# ESP32-S3_4G_LTE_CAT1_V1_1.net
KiCad netlist of a schematic drawn in EAGLE
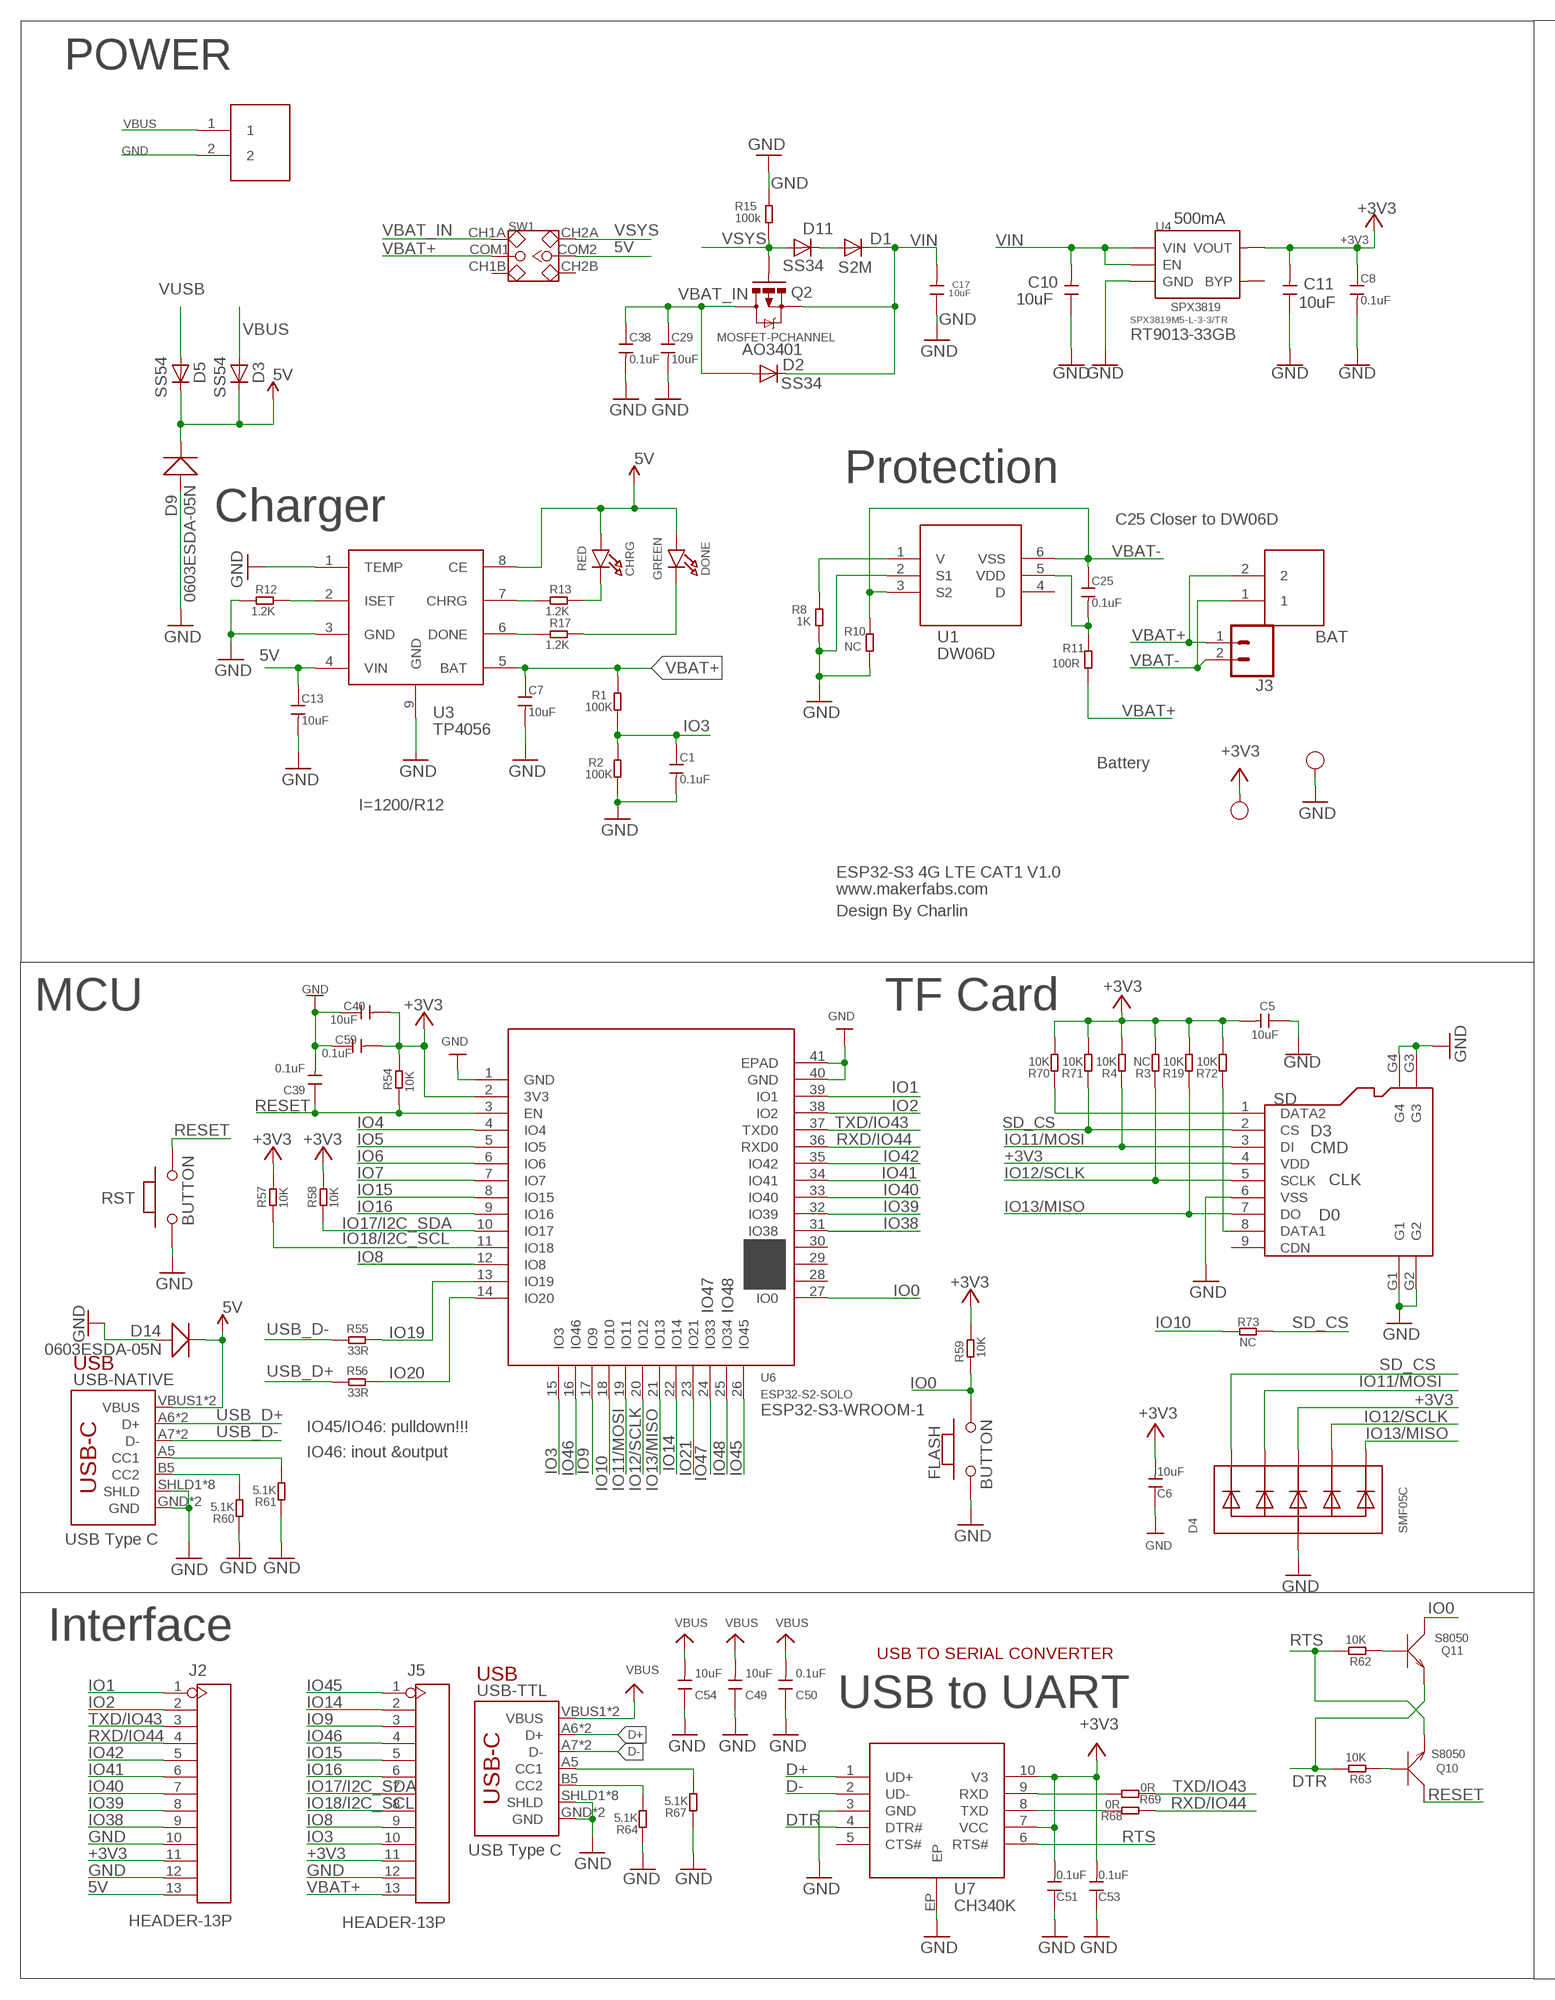
[diagram p0: schematic, sheet 1, part 1 of 2]
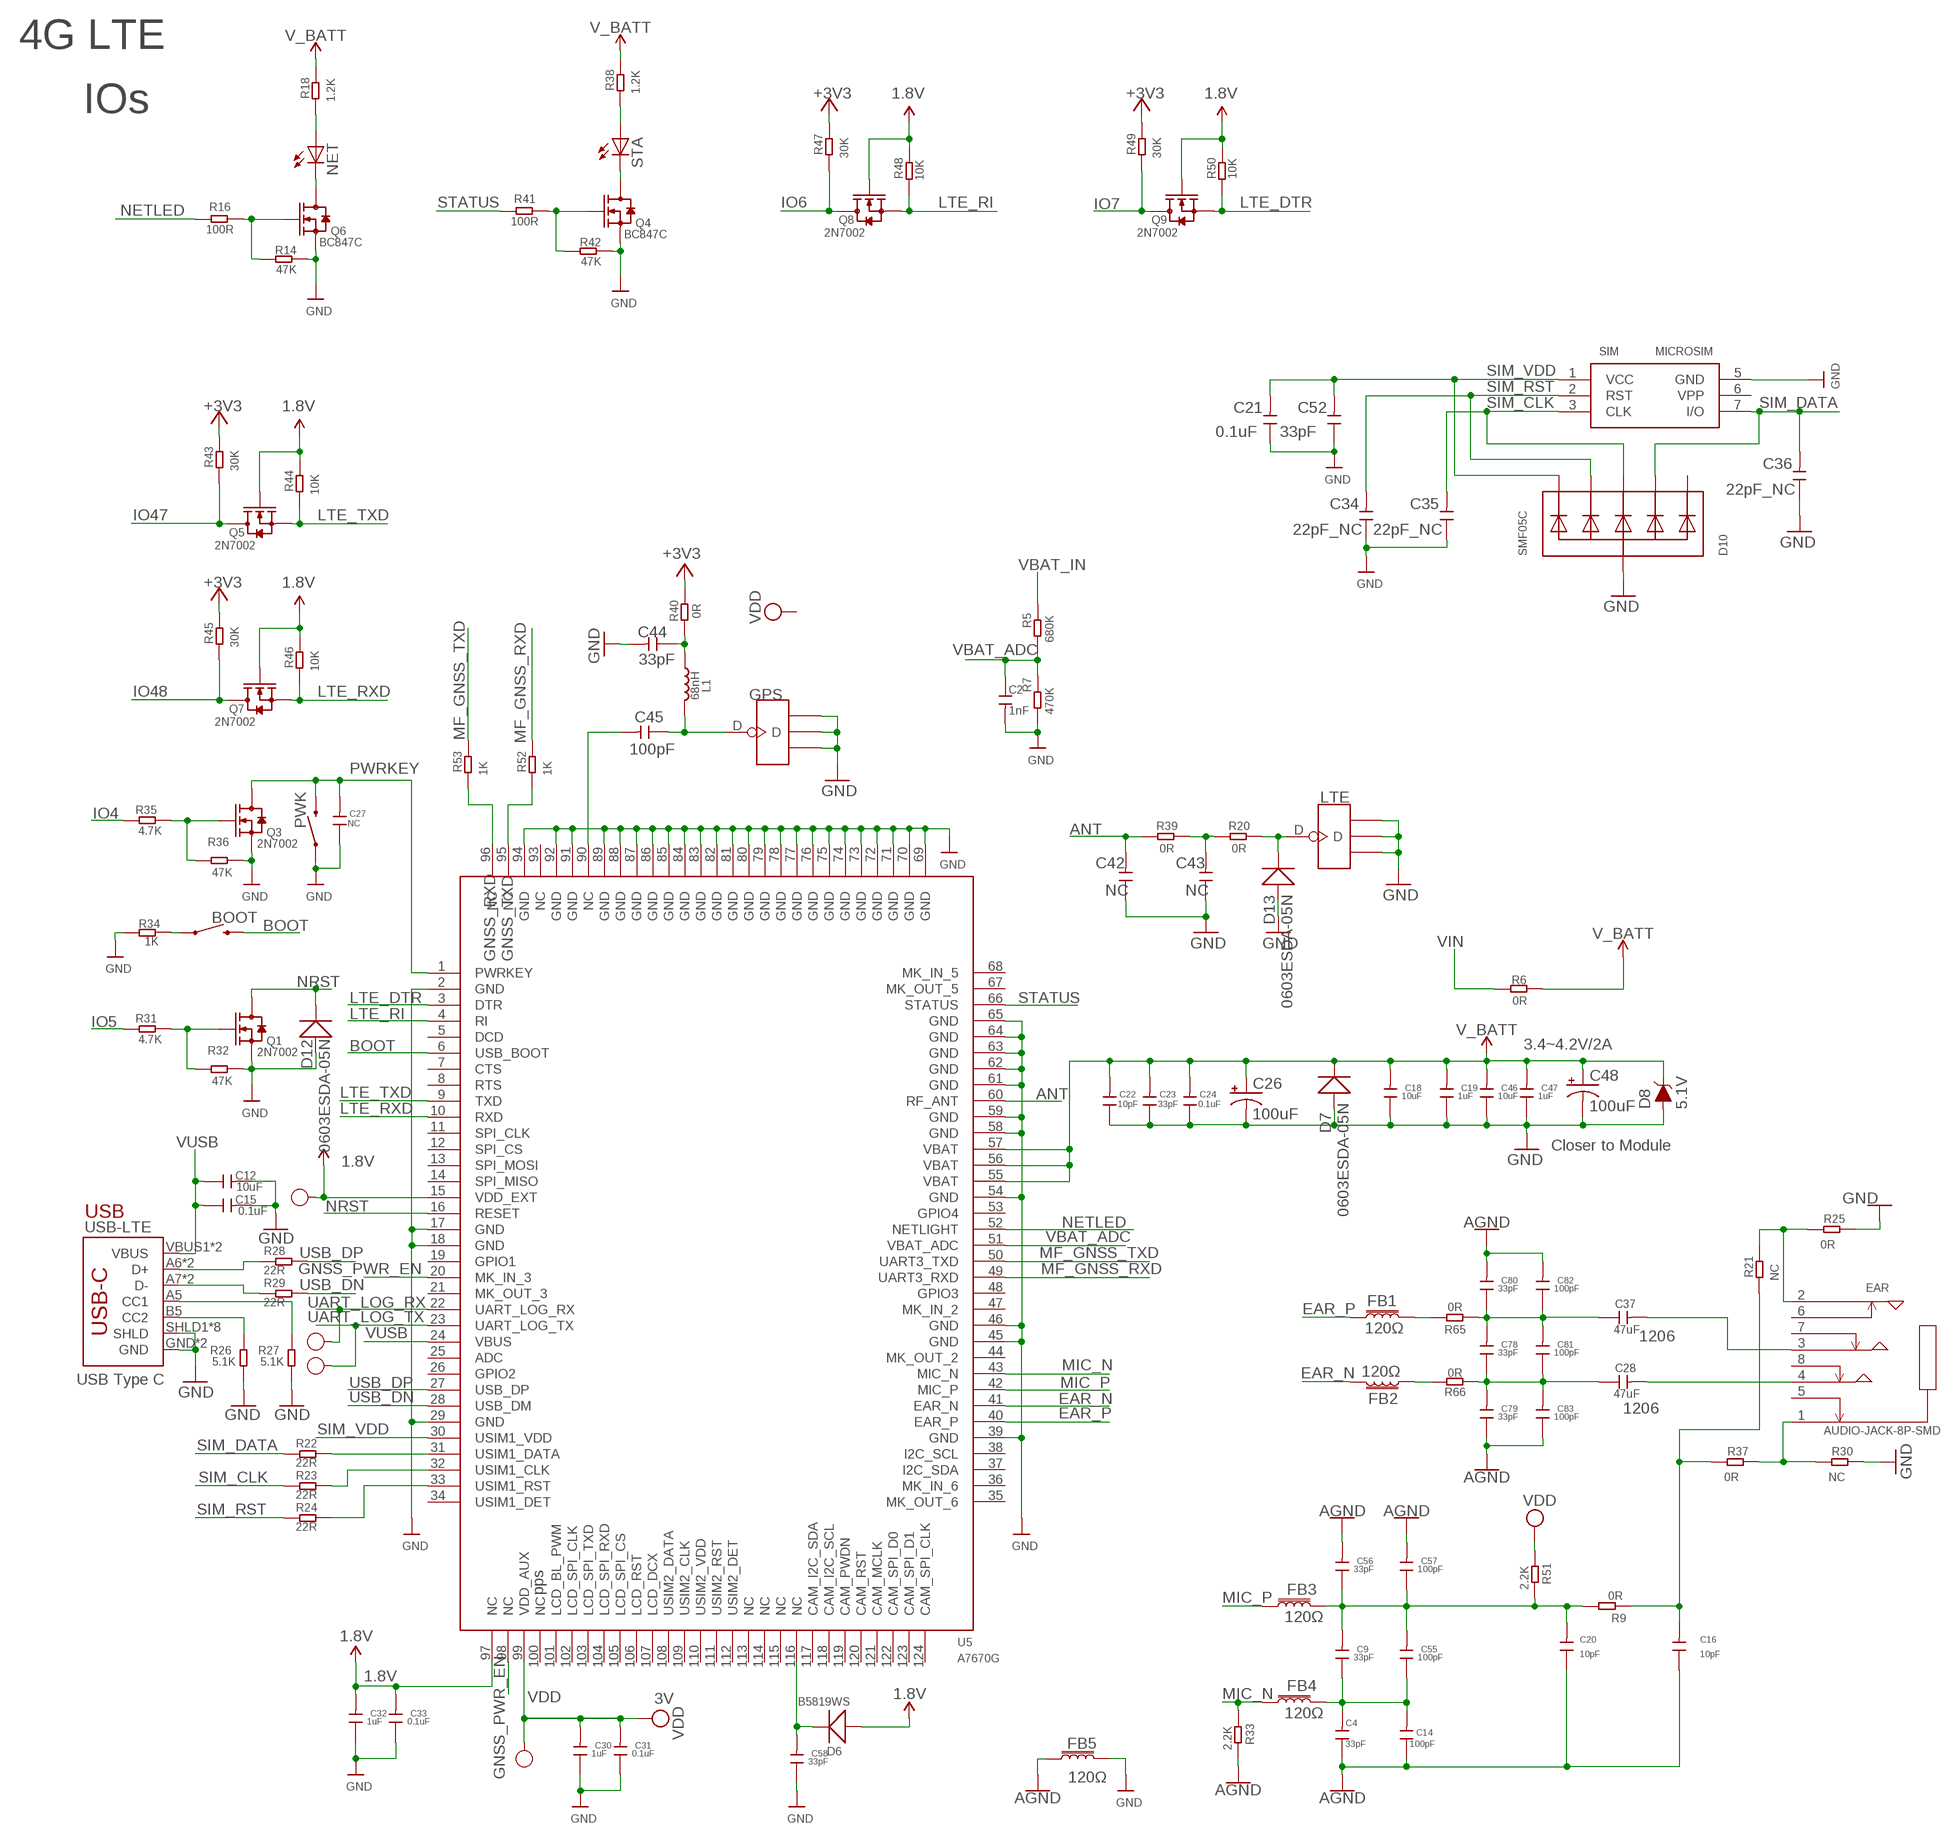
[diagram p1: schematic, sheet 1, part 2 of 2]

(export (version "E")
  (design (tool "Eeschema 10.0.6"))
  (components
    (comp (ref "1V8")
      (value "TEST-POINT'4545'")
      (footprint "eagle-import:TP-D45MIL")
      (fields (field (name "PARTNO") "DNP") (field (name "PARTNO_1") "DNP"))
      (libsource (lib "eagle-import") (part "TEST-POINT'4545'"))
    )
    (comp (ref "3V")
      (value "TEST-POINT'4545'")
      (footprint "eagle-import:TP-D45MIL")
      (fields (field (name "PARTNO") "DNP") (field (name "PARTNO_1") "DNP"))
      (libsource (lib "eagle-import") (part "TEST-POINT'4545'"))
    )
    (comp (ref "3V3")
      (value "TEST-POINT'4545'")
      (footprint "eagle-import:TP-D45MIL")
      (fields (field (name "PARTNO") "DNP") (field (name "PARTNO_1") "DNP"))
      (libsource (lib "eagle-import") (part "TEST-POINT'4545'"))
    )
    (comp (ref "BAT")
      (value "PH2.0-2P-90-DIP")
      (footprint "eagle-import:PH2.0-2P-90-DIP")
      (libsource (lib "eagle-import") (part "PH2.0-2P-90-DIP"))
    )
    (comp (ref "BOOT")
      (value "MOMENTARY-SWITCH-SPST-SMD-6.0X3.5MM")
      (footprint "eagle-import:TACTILE_SWITCH_SMD_6.0X3.5MM")
      (fields (field (name "PROD_ID") "SWCH-00815") (field (name "SF_SKU") "COM-08229"))
      (libsource (lib "eagle-import") (part "MOMENTARY-SWITCH-SPST-SMD-6.0X3.5MM"))
    )
    (comp (ref "C1")
      (value "0.1uF")
      (footprint "eagle-import:0603")
      (libsource (lib "eagle-import") (part "C-0603"))
    )
    (comp (ref "C2")
      (value "1nF")
      (footprint "eagle-import:0603")
      (libsource (lib "eagle-import") (part "C-0603"))
    )
    (comp (ref "C4")
      (value "33pF")
      (footprint "eagle-import:0603")
      (libsource (lib "eagle-import") (part "C-0603"))
    )
    (comp (ref "C5")
      (value "10uF")
      (footprint "eagle-import:DISCRETE_C0603")
      (libsource (lib "eagle-import") (part "DISCRETE_C-0603"))
    )
    (comp (ref "C6")
      (value "10uF")
      (footprint "eagle-import:DISCRETE_C0603")
      (libsource (lib "eagle-import") (part "DISCRETE_C-0603"))
    )
    (comp (ref "C7")
      (value "10uF")
      (footprint "eagle-import:0603")
      (libsource (lib "eagle-import") (part "C-0603"))
    )
    (comp (ref "C8")
      (value "0.1uF")
      (footprint "eagle-import:0603")
      (libsource (lib "eagle-import") (part "C-0603"))
    )
    (comp (ref "C9")
      (value "33pF")
      (footprint "eagle-import:0603")
      (libsource (lib "eagle-import") (part "C-0603"))
    )
    (comp (ref "C10")
      (value "10uF")
      (footprint "eagle-import:0603")
      (libsource (lib "eagle-import") (part "C-0603"))
    )
    (comp (ref "C11")
      (value "10uF")
      (footprint "eagle-import:0603")
      (libsource (lib "eagle-import") (part "C-0603"))
    )
    (comp (ref "C12")
      (value "10uF")
      (footprint "eagle-import:0603")
      (libsource (lib "eagle-import") (part "C-0603"))
    )
    (comp (ref "C13")
      (value "10uF")
      (footprint "eagle-import:0603")
      (libsource (lib "eagle-import") (part "C-0603"))
    )
    (comp (ref "C14")
      (value "100pF")
      (footprint "eagle-import:0603")
      (libsource (lib "eagle-import") (part "C-0603"))
    )
    (comp (ref "C15")
      (value "0.1uF")
      (footprint "eagle-import:0603")
      (libsource (lib "eagle-import") (part "C-0603"))
    )
    (comp (ref "C16")
      (value "10pF")
      (footprint "eagle-import:0603")
      (libsource (lib "eagle-import") (part "C-0603"))
    )
    (comp (ref "C17")
      (value "10uF")
      (footprint "eagle-import:0603")
      (libsource (lib "eagle-import") (part "C-0603"))
    )
    (comp (ref "C18")
      (value "10uF")
      (footprint "eagle-import:0603")
      (libsource (lib "eagle-import") (part "C-0603"))
    )
    (comp (ref "C19")
      (value "1uF")
      (footprint "eagle-import:0603")
      (libsource (lib "eagle-import") (part "C-0603"))
    )
    (comp (ref "C20")
      (value "10pF")
      (footprint "eagle-import:0603")
      (libsource (lib "eagle-import") (part "C-0603"))
    )
    (comp (ref "C21")
      (value "0.1uF")
      (footprint "eagle-import:0603")
      (libsource (lib "eagle-import") (part "C-0603"))
    )
    (comp (ref "C22")
      (value "10pF")
      (footprint "eagle-import:0603")
      (libsource (lib "eagle-import") (part "C-0603"))
    )
    (comp (ref "C23")
      (value "33pF")
      (footprint "eagle-import:0603")
      (libsource (lib "eagle-import") (part "C-0603"))
    )
    (comp (ref "C24")
      (value "0.1uF")
      (footprint "eagle-import:0603")
      (libsource (lib "eagle-import") (part "C-0603"))
    )
    (comp (ref "C25")
      (value "0.1uF")
      (footprint "eagle-import:0603")
      (libsource (lib "eagle-import") (part "C-0603"))
    )
    (comp (ref "C26")
      (value "100uF")
      (footprint "eagle-import:EIA3528")
      (fields (field (name "PROD_ID") "CAP-10790"))
      (libsource (lib "eagle-import") (part "68UF-POLAR-EIA3528-10V-10%(TANT)"))
    )
    (comp (ref "C27")
      (value "NC")
      (footprint "eagle-import:0603")
      (libsource (lib "eagle-import") (part "C-0603"))
    )
    (comp (ref "C28")
      (value "47uF")
      (footprint "eagle-import:DISCRETE_C1206")
      (libsource (lib "eagle-import") (part "DISCRETE_C-1206"))
    )
    (comp (ref "C29")
      (value "10uF")
      (footprint "eagle-import:0603")
      (libsource (lib "eagle-import") (part "C-0603"))
    )
    (comp (ref "C30")
      (value "1uF")
      (footprint "eagle-import:0603")
      (libsource (lib "eagle-import") (part "C-0603"))
    )
    (comp (ref "C31")
      (value "0.1uF")
      (footprint "eagle-import:0603")
      (libsource (lib "eagle-import") (part "C-0603"))
    )
    (comp (ref "C32")
      (value "1uF")
      (footprint "eagle-import:0603")
      (libsource (lib "eagle-import") (part "C-0603"))
    )
    (comp (ref "C33")
      (value "0.1uF")
      (footprint "eagle-import:0603")
      (libsource (lib "eagle-import") (part "C-0603"))
    )
    (comp (ref "C34")
      (value "22pF_NC")
      (footprint "eagle-import:0603")
      (libsource (lib "eagle-import") (part "C-0603"))
    )
    (comp (ref "C35")
      (value "22pF_NC")
      (footprint "eagle-import:0603")
      (libsource (lib "eagle-import") (part "C-0603"))
    )
    (comp (ref "C36")
      (value "22pF_NC")
      (footprint "eagle-import:0603")
      (libsource (lib "eagle-import") (part "C-0603"))
    )
    (comp (ref "C37")
      (value "47uF")
      (footprint "eagle-import:DISCRETE_C1206")
      (libsource (lib "eagle-import") (part "DISCRETE_C-1206"))
    )
    (comp (ref "C38")
      (value "0.1uF")
      (footprint "eagle-import:0603")
      (libsource (lib "eagle-import") (part "C-0603"))
    )
    (comp (ref "C39")
      (value "0.1uF")
      (footprint "eagle-import:DISCRETE_C0603")
      (libsource (lib "eagle-import") (part "DISCRETE_C-0603"))
    )
    (comp (ref "C40")
      (value "10uF")
      (footprint "eagle-import:DISCRETE_C0603")
      (libsource (lib "eagle-import") (part "DISCRETE_C-0603"))
    )
    (comp (ref "C42")
      (value "NC")
      (footprint "eagle-import:0603")
      (libsource (lib "eagle-import") (part "C-0603"))
    )
    (comp (ref "C43")
      (value "NC")
      (footprint "eagle-import:0603")
      (libsource (lib "eagle-import") (part "C-0603"))
    )
    (comp (ref "C44")
      (value "33pF")
      (footprint "eagle-import:0603")
      (libsource (lib "eagle-import") (part "C-0603"))
    )
    (comp (ref "C45")
      (value "100pF")
      (footprint "eagle-import:0603")
      (libsource (lib "eagle-import") (part "C-0603"))
    )
    (comp (ref "C46")
      (value "10uF")
      (footprint "eagle-import:0603")
      (libsource (lib "eagle-import") (part "C-0603"))
    )
    (comp (ref "C47")
      (value "1uF")
      (footprint "eagle-import:0603")
      (libsource (lib "eagle-import") (part "C-0603"))
    )
    (comp (ref "C48")
      (value "100uF")
      (footprint "eagle-import:EIA3528")
      (libsource (lib "eagle-import") (part "68UF-POLAR-EIA3528-10V-10%(TANT)"))
    )
    (comp (ref "C49")
      (value "10uF")
      (footprint "eagle-import:DISCRETE_C0603")
      (libsource (lib "eagle-import") (part "DISCRETE_C-0603"))
    )
    (comp (ref "C50")
      (value "0.1uF")
      (footprint "eagle-import:DISCRETE_C0603")
      (libsource (lib "eagle-import") (part "DISCRETE_C-0603"))
    )
    (comp (ref "C51")
      (value "0.1uF")
      (footprint "eagle-import:DISCRETE_C0603")
      (libsource (lib "eagle-import") (part "DISCRETE_C-0603"))
    )
    (comp (ref "C52")
      (value "33pF")
      (footprint "eagle-import:0603")
      (libsource (lib "eagle-import") (part "C-0603"))
    )
    (comp (ref "C53")
      (value "0.1uF")
      (footprint "eagle-import:DISCRETE_C0603")
      (libsource (lib "eagle-import") (part "DISCRETE_C-0603"))
    )
    (comp (ref "C54")
      (value "10uF")
      (footprint "eagle-import:DISCRETE_C0603")
      (libsource (lib "eagle-import") (part "DISCRETE_C-0603"))
    )
    (comp (ref "C55")
      (value "100pF")
      (footprint "eagle-import:0603")
      (libsource (lib "eagle-import") (part "C-0603"))
    )
    (comp (ref "C56")
      (value "33pF")
      (footprint "eagle-import:0603")
      (libsource (lib "eagle-import") (part "C-0603"))
    )
    (comp (ref "C57")
      (value "100pF")
      (footprint "eagle-import:0603")
      (libsource (lib "eagle-import") (part "C-0603"))
    )
    (comp (ref "C58")
      (value "33pF")
      (footprint "eagle-import:0603")
      (libsource (lib "eagle-import") (part "C-0603"))
    )
    (comp (ref "C59")
      (value "0.1uF")
      (footprint "eagle-import:DISCRETE_C0603")
      (libsource (lib "eagle-import") (part "DISCRETE_C-0603"))
    )
    (comp (ref "C78")
      (value "33pF")
      (footprint "eagle-import:0603")
      (libsource (lib "eagle-import") (part "C-0603"))
    )
    (comp (ref "C79")
      (value "33pF")
      (footprint "eagle-import:0603")
      (libsource (lib "eagle-import") (part "C-0603"))
    )
    (comp (ref "C80")
      (value "33pF")
      (footprint "eagle-import:0603")
      (libsource (lib "eagle-import") (part "C-0603"))
    )
    (comp (ref "C81")
      (value "100pF")
      (footprint "eagle-import:0603")
      (libsource (lib "eagle-import") (part "C-0603"))
    )
    (comp (ref "C82")
      (value "100pF")
      (footprint "eagle-import:0603")
      (libsource (lib "eagle-import") (part "C-0603"))
    )
    (comp (ref "C83")
      (value "100pF")
      (footprint "eagle-import:0603")
      (libsource (lib "eagle-import") (part "C-0603"))
    )
    (comp (ref "CHRG")
      (value "RED")
      (footprint "eagle-import:CHIPLED_0805_NOOUTLINE")
      (libsource (lib "eagle-import") (part "LED0805_NOOUTLINE"))
    )
    (comp (ref "D1")
      (value "S2M")
      (footprint "eagle-import:DO-214AC")
      (libsource (lib "eagle-import") (part "DIODE-DO-214AC"))
    )
    (comp (ref "D2")
      (value "SS34")
      (footprint "eagle-import:DO-214AC")
      (libsource (lib "eagle-import") (part "DIODE-DO-214AC"))
    )
    (comp (ref "D3")
      (value "SS54")
      (footprint "eagle-import:DO-214AC")
      (libsource (lib "eagle-import") (part "DIODE-DO-214AC"))
    )
    (comp (ref "D4")
      (value "SMF05C")
      (footprint "eagle-import:SOT363")
      (libsource (lib "eagle-import") (part "TVSARRAY_5LANE"))
    )
    (comp (ref "D5")
      (value "SS54")
      (footprint "eagle-import:DO-214AC")
      (libsource (lib "eagle-import") (part "DIODE-DO-214AC"))
    )
    (comp (ref "D6")
      (value "B5819WS")
      (footprint "eagle-import:SOD323")
      (libsource (lib "eagle-import") (part "D'0805'"))
    )
    (comp (ref "D7")
      (value "0603ESDA-05N")
      (footprint "eagle-import:DISCRETE_SOD523")
      (libsource (lib "eagle-import") (part "DISCRETE_D0603"))
    )
    (comp (ref "D8")
      (value "5.1V")
      (footprint "eagle-import:SOD-323")
      (libsource (lib "eagle-import") (part "DIODE-ZENER-MMSZ5232BS"))
    )
    (comp (ref "D9")
      (value "0603ESDA-05N")
      (footprint "eagle-import:DISCRETE_SOD523")
      (libsource (lib "eagle-import") (part "DISCRETE_D0603"))
    )
    (comp (ref "D10")
      (value "SMF05C")
      (footprint "eagle-import:SOT363")
      (libsource (lib "eagle-import") (part "TVSARRAY_5LANE"))
    )
    (comp (ref "D11")
      (value "SS34")
      (footprint "eagle-import:DO-214AC")
      (libsource (lib "eagle-import") (part "DIODE-DO-214AC"))
    )
    (comp (ref "D12")
      (value "0603ESDA-05N")
      (footprint "eagle-import:DISCRETE_SOD523")
      (libsource (lib "eagle-import") (part "DISCRETE_D0603"))
    )
    (comp (ref "D13")
      (value "0603ESDA-05N")
      (footprint "eagle-import:DISCRETE_SOD523")
      (libsource (lib "eagle-import") (part "DISCRETE_D0603"))
    )
    (comp (ref "D14")
      (value "0603ESDA-05N")
      (footprint "eagle-import:DISCRETE_SOD523")
      (libsource (lib "eagle-import") (part "DISCRETE_D0603"))
    )
    (comp (ref "DONE")
      (value "GREEN")
      (footprint "eagle-import:CHIPLED_0805_NOOUTLINE")
      (libsource (lib "eagle-import") (part "LED0805_NOOUTLINE"))
    )
    (comp (ref "EAR")
      (value "AUDIO-JACK-8P-SMD")
      (footprint "eagle-import:AUDIO8P-SMD-3.5-14.5X6.1X4.0MM")
      (libsource (lib "eagle-import") (part "AUDIO-JACK-8P-SMD'PJ-393'"))
    )
    (comp (ref "FB1")
      (value "120Ω")
      (footprint "eagle-import:0603")
      (libsource (lib "eagle-import") (part "FERRITE_BEAD-0603"))
    )
    (comp (ref "FB2")
      (value "120Ω")
      (footprint "eagle-import:0603")
      (fields (field (name "PROD_ID") "NDUC-13805"))
      (libsource (lib "eagle-import") (part "FERRITE_BEAD-0603"))
    )
    (comp (ref "FB3")
      (value "120Ω")
      (footprint "eagle-import:0603")
      (fields (field (name "PROD_ID") "NDUC-13805"))
      (libsource (lib "eagle-import") (part "FERRITE_BEAD-0603"))
    )
    (comp (ref "FB4")
      (value "120Ω")
      (footprint "eagle-import:0603")
      (fields (field (name "PROD_ID") "NDUC-13805"))
      (libsource (lib "eagle-import") (part "FERRITE_BEAD-0603"))
    )
    (comp (ref "FB5")
      (value "120Ω")
      (footprint "eagle-import:0603")
      (fields (field (name "PROD_ID") "NDUC-13805"))
      (libsource (lib "eagle-import") (part "FERRITE_BEAD-0603"))
    )
    (comp (ref "FLASH")
      (value "BUTTON")
      (footprint "eagle-import:157SW")
      (libsource (lib "eagle-import") (part "PB157"))
    )
    (comp (ref "GND")
      (value "TEST-POINT'4545'")
      (footprint "eagle-import:TP-D45MIL")
      (fields (field (name "PARTNO") "DNP") (field (name "PARTNO_1") "DNP"))
      (libsource (lib "eagle-import") (part "TEST-POINT'4545'"))
    )
    (comp (ref "GPS")
      (value "ANTENNA-U-FL")
      (footprint "eagle-import:4P-U-FL")
      (libsource (lib "eagle-import") (part "ANTENNA-U-FL"))
    )
    (comp (ref "J1")
      (value "PH2.0-2P-90-DIP")
      (footprint "eagle-import:PH2.0-2P-90-DIP")
      (libsource (lib "eagle-import") (part "PH2.0-2P-90-DIP"))
    )
    (comp (ref "J2")
      (value "HEADER-13P")
      (footprint "eagle-import:13P-2.54")
      (libsource (lib "eagle-import") (part "HEADER-13P"))
    )
    (comp (ref "J3")
      (value "CONN_02LOCK")
      (footprint "eagle-import:1X02_LOCK")
      (libsource (lib "eagle-import") (part "CONN_02LOCK"))
    )
    (comp (ref "J5")
      (value "HEADER-13P")
      (footprint "eagle-import:13P-2.54")
      (libsource (lib "eagle-import") (part "HEADER-13P"))
    )
    (comp (ref "L1")
      (value "68nH")
      (footprint "eagle-import:L0603")
      (libsource (lib "eagle-import") (part "L'0603'"))
    )
    (comp (ref "LTE")
      (value "ANTENNA-U-FL")
      (footprint "eagle-import:4P-U-FL")
      (libsource (lib "eagle-import") (part "ANTENNA-U-FL"))
    )
    (comp (ref "NET")
      (value "NET")
      (footprint "eagle-import:CHIP-LED0805")
      (libsource (lib "eagle-import") (part "LEDCHIP-LED0805"))
    )
    (comp (ref "PWK")
      (value "MOMENTARY-SWITCH-SPST-SMD-6.0X3.5MM")
      (footprint "eagle-import:TACTILE_SWITCH_SMD_6.0X3.5MM")
      (libsource (lib "eagle-import") (part "MOMENTARY-SWITCH-SPST-SMD-6.0X3.5MM"))
    )
    (comp (ref "Q1")
      (value "2N7002")
      (footprint "eagle-import:SOT23")
      (libsource (lib "eagle-import") (part "MOSFET-N'SOT23'"))
    )
    (comp (ref "Q2")
      (value "MOSFET-PCHANNEL")
      (footprint "eagle-import:SOT23-3")
      (libsource (lib "eagle-import") (part "MOSFET-PCHANNEL"))
    )
    (comp (ref "Q3")
      (value "2N7002")
      (footprint "eagle-import:SOT23")
      (libsource (lib "eagle-import") (part "MOSFET-N'SOT23'"))
    )
    (comp (ref "Q4")
      (value "BC847C")
      (footprint "eagle-import:SOT23")
      (libsource (lib "eagle-import") (part "MOSFET-N'SOT23'"))
    )
    (comp (ref "Q5")
      (value "2N7002")
      (footprint "eagle-import:SOT23")
      (libsource (lib "eagle-import") (part "MOSFET-N'SOT23'"))
    )
    (comp (ref "Q6")
      (value "BC847C")
      (footprint "eagle-import:SOT23")
      (libsource (lib "eagle-import") (part "MOSFET-N'SOT23'"))
    )
    (comp (ref "Q7")
      (value "2N7002")
      (footprint "eagle-import:SOT23")
      (libsource (lib "eagle-import") (part "MOSFET-N'SOT23'"))
    )
    (comp (ref "Q8")
      (value "2N7002")
      (footprint "eagle-import:SOT23")
      (libsource (lib "eagle-import") (part "MOSFET-N'SOT23'"))
    )
    (comp (ref "Q9")
      (value "2N7002")
      (footprint "eagle-import:SOT23")
      (libsource (lib "eagle-import") (part "MOSFET-N'SOT23'"))
    )
    (comp (ref "Q10")
      (value "S8050")
      (footprint "eagle-import:SOT23")
      (libsource (lib "eagle-import") (part "TRANSISTOR-NPN-SOT23"))
    )
    (comp (ref "Q11")
      (value "S8050")
      (footprint "eagle-import:SOT23")
      (libsource (lib "eagle-import") (part "TRANSISTOR-NPN-SOT23"))
    )
    (comp (ref "R1")
      (value "100K")
      (footprint "eagle-import:R0603")
      (libsource (lib "eagle-import") (part "R-0603"))
    )
    (comp (ref "R2")
      (value "100K")
      (footprint "eagle-import:R0603")
      (libsource (lib "eagle-import") (part "R-0603"))
    )
    (comp (ref "R3")
      (value "NC")
      (footprint "eagle-import:DISCRETE_R0603")
      (libsource (lib "eagle-import") (part "DISCRETE_R-0603"))
    )
    (comp (ref "R4")
      (value "10K")
      (footprint "eagle-import:DISCRETE_R0603")
      (libsource (lib "eagle-import") (part "DISCRETE_R-0603"))
    )
    (comp (ref "R5")
      (value "680K")
      (footprint "eagle-import:R0603")
      (libsource (lib "eagle-import") (part "R-0603"))
    )
    (comp (ref "R6")
      (value "0R")
      (footprint "eagle-import:R0603")
      (libsource (lib "eagle-import") (part "R-0603"))
    )
    (comp (ref "R7")
      (value "470K")
      (footprint "eagle-import:R0603")
      (libsource (lib "eagle-import") (part "R-0603"))
    )
    (comp (ref "R8")
      (value "1K")
      (footprint "eagle-import:R0603")
      (libsource (lib "eagle-import") (part "R-0603"))
    )
    (comp (ref "R9")
      (value "0R")
      (footprint "eagle-import:R0603")
      (libsource (lib "eagle-import") (part "R-0603"))
    )
    (comp (ref "R10")
      (value "NC")
      (footprint "eagle-import:R0603")
      (libsource (lib "eagle-import") (part "R-0603"))
    )
    (comp (ref "R11")
      (value "100R")
      (footprint "eagle-import:R0603")
      (libsource (lib "eagle-import") (part "R-0603"))
    )
    (comp (ref "R12")
      (value "1.2K")
      (footprint "eagle-import:R0603")
      (libsource (lib "eagle-import") (part "R-0603"))
    )
    (comp (ref "R13")
      (value "1.2K")
      (footprint "eagle-import:R0603")
      (libsource (lib "eagle-import") (part "R-0603"))
    )
    (comp (ref "R14")
      (value "47K")
      (footprint "eagle-import:R0603")
      (libsource (lib "eagle-import") (part "R-0603"))
    )
    (comp (ref "R15")
      (value "100k")
      (footprint "eagle-import:R0603")
      (libsource (lib "eagle-import") (part "R-0603"))
    )
    (comp (ref "R16")
      (value "100R")
      (footprint "eagle-import:R0603")
      (libsource (lib "eagle-import") (part "R-0603"))
    )
    (comp (ref "R17")
      (value "1.2K")
      (footprint "eagle-import:R0603")
      (libsource (lib "eagle-import") (part "R-0603"))
    )
    (comp (ref "R18")
      (value "1.2K")
      (footprint "eagle-import:R0603")
      (libsource (lib "eagle-import") (part "R-0603"))
    )
    (comp (ref "R19")
      (value "10K")
      (footprint "eagle-import:DISCRETE_R0603")
      (libsource (lib "eagle-import") (part "DISCRETE_R-0603"))
    )
    (comp (ref "R20")
      (value "0R")
      (footprint "eagle-import:R0603")
      (libsource (lib "eagle-import") (part "R-0603"))
    )
    (comp (ref "R21")
      (value "NC")
      (footprint "eagle-import:R0603")
      (libsource (lib "eagle-import") (part "R-0603"))
    )
    (comp (ref "R22")
      (value "22R")
      (footprint "eagle-import:R0603")
      (libsource (lib "eagle-import") (part "R-0603"))
    )
    (comp (ref "R23")
      (value "22R")
      (footprint "eagle-import:R0603")
      (libsource (lib "eagle-import") (part "R-0603"))
    )
    (comp (ref "R24")
      (value "22R")
      (footprint "eagle-import:R0603")
      (libsource (lib "eagle-import") (part "R-0603"))
    )
    (comp (ref "R25")
      (value "0R")
      (footprint "eagle-import:R0603")
      (libsource (lib "eagle-import") (part "R-0603"))
    )
    (comp (ref "R26")
      (value "5.1K")
      (footprint "eagle-import:R0603")
      (libsource (lib "eagle-import") (part "R-0603"))
    )
    (comp (ref "R27")
      (value "5.1K")
      (footprint "eagle-import:R0603")
      (libsource (lib "eagle-import") (part "R-0603"))
    )
    (comp (ref "R28")
      (value "22R")
      (footprint "eagle-import:R0603")
      (libsource (lib "eagle-import") (part "R-0603"))
    )
    (comp (ref "R29")
      (value "22R")
      (footprint "eagle-import:R0603")
      (libsource (lib "eagle-import") (part "R-0603"))
    )
    (comp (ref "R30")
      (value "NC")
      (footprint "eagle-import:R0603")
      (libsource (lib "eagle-import") (part "R-0603"))
    )
    (comp (ref "R31")
      (value "4.7K")
      (footprint "eagle-import:R0603")
      (libsource (lib "eagle-import") (part "R-0603"))
    )
    (comp (ref "R32")
      (value "47K")
      (footprint "eagle-import:R0603")
      (libsource (lib "eagle-import") (part "R-0603"))
    )
    (comp (ref "R33")
      (value "2.2K")
      (footprint "eagle-import:R0603")
      (libsource (lib "eagle-import") (part "R-0603"))
    )
    (comp (ref "R34")
      (value "1K")
      (footprint "eagle-import:R0603")
      (libsource (lib "eagle-import") (part "R-0603"))
    )
    (comp (ref "R35")
      (value "4.7K")
      (footprint "eagle-import:R0603")
      (libsource (lib "eagle-import") (part "R-0603"))
    )
    (comp (ref "R36")
      (value "47K")
      (footprint "eagle-import:R0603")
      (libsource (lib "eagle-import") (part "R-0603"))
    )
    (comp (ref "R37")
      (value "0R")
      (footprint "eagle-import:R0603")
      (libsource (lib "eagle-import") (part "R-0603"))
    )
    (comp (ref "R38")
      (value "1.2K")
      (footprint "eagle-import:R0603")
      (libsource (lib "eagle-import") (part "R-0603"))
    )
    (comp (ref "R39")
      (value "0R")
      (footprint "eagle-import:R0603")
      (libsource (lib "eagle-import") (part "R-0603"))
    )
    (comp (ref "R40")
      (value "0R")
      (footprint "eagle-import:R0603")
      (libsource (lib "eagle-import") (part "R-0603"))
    )
    (comp (ref "R41")
      (value "100R")
      (footprint "eagle-import:R0603")
      (libsource (lib "eagle-import") (part "R-0603"))
    )
    (comp (ref "R42")
      (value "47K")
      (footprint "eagle-import:R0603")
      (libsource (lib "eagle-import") (part "R-0603"))
    )
    (comp (ref "R43")
      (value "30K")
      (footprint "eagle-import:R0603")
      (libsource (lib "eagle-import") (part "R-0603"))
    )
    (comp (ref "R44")
      (value "10K")
      (footprint "eagle-import:R0603")
      (libsource (lib "eagle-import") (part "R-0603"))
    )
    (comp (ref "R45")
      (value "30K")
      (footprint "eagle-import:R0603")
      (libsource (lib "eagle-import") (part "R-0603"))
    )
    (comp (ref "R46")
      (value "10K")
      (footprint "eagle-import:R0603")
      (libsource (lib "eagle-import") (part "R-0603"))
    )
    (comp (ref "R47")
      (value "30K")
      (footprint "eagle-import:R0603")
      (libsource (lib "eagle-import") (part "R-0603"))
    )
    (comp (ref "R48")
      (value "10K")
      (footprint "eagle-import:R0603")
      (libsource (lib "eagle-import") (part "R-0603"))
    )
    (comp (ref "R49")
      (value "30K")
      (footprint "eagle-import:R0603")
      (libsource (lib "eagle-import") (part "R-0603"))
    )
    (comp (ref "R50")
      (value "10K")
      (footprint "eagle-import:R0603")
      (libsource (lib "eagle-import") (part "R-0603"))
    )
    (comp (ref "R51")
      (value "2.2K")
      (footprint "eagle-import:R0603")
      (libsource (lib "eagle-import") (part "R-0603"))
    )
    (comp (ref "R52")
      (value "1K")
      (footprint "eagle-import:R0603")
      (libsource (lib "eagle-import") (part "R-0603"))
    )
    (comp (ref "R53")
      (value "1K")
      (footprint "eagle-import:R0603")
      (libsource (lib "eagle-import") (part "R-0603"))
    )
    (comp (ref "R54")
      (value "10K")
      (footprint "eagle-import:R0603")
      (libsource (lib "eagle-import") (part "R-0603"))
    )
    (comp (ref "R55")
      (value "33R")
      (footprint "eagle-import:R0603")
      (libsource (lib "eagle-import") (part "R-0603"))
    )
    (comp (ref "R56")
      (value "33R")
      (footprint "eagle-import:R0603")
      (libsource (lib "eagle-import") (part "R-0603"))
    )
    (comp (ref "R57")
      (value "10K")
      (footprint "eagle-import:R0603")
      (libsource (lib "eagle-import") (part "R-0603"))
    )
    (comp (ref "R58")
      (value "10K")
      (footprint "eagle-import:R0603")
      (libsource (lib "eagle-import") (part "R-0603"))
    )
    (comp (ref "R59")
      (value "10K")
      (footprint "eagle-import:R0603")
      (libsource (lib "eagle-import") (part "R-0603"))
    )
    (comp (ref "R60")
      (value "5.1K")
      (footprint "eagle-import:DISCRETE_R0603")
      (libsource (lib "eagle-import") (part "DISCRETE_R-0603"))
    )
    (comp (ref "R61")
      (value "5.1K")
      (footprint "eagle-import:DISCRETE_R0603")
      (libsource (lib "eagle-import") (part "DISCRETE_R-0603"))
    )
    (comp (ref "R62")
      (value "10K")
      (footprint "eagle-import:R0603")
      (libsource (lib "eagle-import") (part "R-0603"))
    )
    (comp (ref "R63")
      (value "10K")
      (footprint "eagle-import:R0603")
      (libsource (lib "eagle-import") (part "R-0603"))
    )
    (comp (ref "R64")
      (value "5.1K")
      (footprint "eagle-import:DISCRETE_R0603")
      (libsource (lib "eagle-import") (part "DISCRETE_R-0603"))
    )
    (comp (ref "R65")
      (value "0R")
      (footprint "eagle-import:R0603")
      (libsource (lib "eagle-import") (part "R-0603"))
    )
    (comp (ref "R66")
      (value "0R")
      (footprint "eagle-import:R0603")
      (libsource (lib "eagle-import") (part "R-0603"))
    )
    (comp (ref "R67")
      (value "5.1K")
      (footprint "eagle-import:DISCRETE_R0603")
      (libsource (lib "eagle-import") (part "DISCRETE_R-0603"))
    )
    (comp (ref "R68")
      (value "0R")
      (footprint "eagle-import:R0603")
      (libsource (lib "eagle-import") (part "R-0603"))
    )
    (comp (ref "R69")
      (value "0R")
      (footprint "eagle-import:R0603")
      (libsource (lib "eagle-import") (part "R-0603"))
    )
    (comp (ref "R70")
      (value "10K")
      (footprint "eagle-import:DISCRETE_R0603")
      (libsource (lib "eagle-import") (part "DISCRETE_R-0603"))
    )
    (comp (ref "R71")
      (value "10K")
      (footprint "eagle-import:DISCRETE_R0603")
      (libsource (lib "eagle-import") (part "DISCRETE_R-0603"))
    )
    (comp (ref "R72")
      (value "10K")
      (footprint "eagle-import:DISCRETE_R0603")
      (libsource (lib "eagle-import") (part "DISCRETE_R-0603"))
    )
    (comp (ref "R73")
      (value "NC")
      (footprint "eagle-import:R0603")
      (libsource (lib "eagle-import") (part "R-0603"))
    )
    (comp (ref "RST")
      (value "BUTTON")
      (footprint "eagle-import:157SW")
      (libsource (lib "eagle-import") (part "PB157"))
    )
    (comp (ref "RX")
      (value "TEST-POINT'4545'")
      (footprint "eagle-import:TP-D45MIL")
      (fields (field (name "PARTNO") "DNP") (field (name "PARTNO_1") "DNP"))
      (libsource (lib "eagle-import") (part "TEST-POINT'4545'"))
    )
    (comp (ref "SD")
      (value "HOLDER-MICROSD-9P")
      (footprint "eagle-import:9P-SMD-W_-RING")
      (libsource (lib "eagle-import") (part "HOLDER-MICROSD-9P"))
    )
    (comp (ref "SIM")
      (value "MICROSIM")
      (footprint "eagle-import:MICROSIM")
      (libsource (lib "eagle-import") (part "MICROSIM"))
    )
    (comp (ref "STA")
      (value "NET")
      (footprint "eagle-import:CHIP-LED0805")
      (libsource (lib "eagle-import") (part "LEDCHIP-LED0805"))
    )
    (comp (ref "SW1")
      (value "SWITCH-2CH-6P")
      (footprint "eagle-import:6P-2CH-2.54-7.6X3.0")
      (libsource (lib "eagle-import") (part "SWITCH-2CH-6P"))
    )
    (comp (ref "TX")
      (value "TEST-POINT'4545'")
      (footprint "eagle-import:TP-D45MIL")
      (fields (field (name "PARTNO") "DNP") (field (name "PARTNO_1") "DNP"))
      (libsource (lib "eagle-import") (part "TEST-POINT'4545'"))
    )
    (comp (ref "U1")
      (value "DW06D")
      (footprint "eagle-import:SOT-23-6")
      (libsource (lib "eagle-import") (part "DW06D"))
    )
    (comp (ref "U3")
      (value "TP4056")
      (footprint "eagle-import:SOP8-1.27P")
      (libsource (lib "eagle-import") (part "TP4056"))
    )
    (comp (ref "U4")
      (value "SPX3819")
      (footprint "eagle-import:SOT23-5")
      (libsource (lib "eagle-import") (part "SPX3819"))
    )
    (comp (ref "U5")
      (value "A7670G")
      (footprint "eagle-import:A7670G")
      (libsource (lib "eagle-import") (part "A7670G"))
    )
    (comp (ref "U6")
      (value "ESP32­S2­SOLO")
      (footprint "eagle-import:ESP32-­S2-­SOLO")
      (libsource (lib "eagle-import") (part "ESP32­S2­SOLO"))
    )
    (comp (ref "U7")
      (value "CH340K")
      (footprint "eagle-import:ESOP-10-EP-150MIL")
      (libsource (lib "eagle-import") (part "CH340K"))
    )
    (comp (ref "USB-LTE")
      (value "USB_C5")
      (footprint "eagle-import:USB-C-16P-5")
      (libsource (lib "eagle-import") (part "USB_C5"))
    )
    (comp (ref "USB-NATIVE")
      (value "USB_C5")
      (footprint "eagle-import:USB-C-16P-5")
      (libsource (lib "eagle-import") (part "USB_C5"))
    )
    (comp (ref "USB-TTL")
      (value "USB_C5")
      (footprint "eagle-import:USB-C-16P-5")
      (libsource (lib "eagle-import") (part "USB_C5"))
    )
  )
  (nets
    (net (code "1") (name "+3V3") (class "Default")
      (node (ref "3V3") (pin "T") (pinfunction "T_T") (pintype "bidirectional"))
      (node (ref "C11") (pin "2") (pinfunction "2_2") (pintype "passive"))
      (node (ref "C40") (pin "2") (pinfunction "2_2") (pintype "passive"))
      (node (ref "C5") (pin "2") (pinfunction "2_2") (pintype "passive"))
      (node (ref "C51") (pin "2") (pinfunction "2_2") (pintype "passive"))
      (node (ref "C53") (pin "2") (pinfunction "2_2") (pintype "passive"))
      (node (ref "C59") (pin "2") (pinfunction "2_2") (pintype "passive"))
      (node (ref "C6") (pin "2") (pinfunction "2_2") (pintype "passive"))
      (node (ref "C8") (pin "1") (pinfunction "1_1") (pintype "passive"))
      (node (ref "D4") (pin "4") (pinfunction "C3_4") (pintype "passive"))
      (node (ref "J2") (pin "11") (pinfunction "11_11") (pintype "bidirectional"))
      (node (ref "J5") (pin "11") (pinfunction "11_11") (pintype "bidirectional"))
      (node (ref "R19") (pin "2") (pinfunction "2_2") (pintype "passive"))
      (node (ref "R3") (pin "2") (pinfunction "2_2") (pintype "passive"))
      (node (ref "R4") (pin "2") (pinfunction "2_2") (pintype "passive"))
      (node (ref "R40") (pin "2") (pinfunction "2_2") (pintype "passive"))
      (node (ref "R43") (pin "2") (pinfunction "2_2") (pintype "passive"))
      (node (ref "R45") (pin "2") (pinfunction "2_2") (pintype "passive"))
      (node (ref "R47") (pin "2") (pinfunction "2_2") (pintype "passive"))
      (node (ref "R49") (pin "2") (pinfunction "2_2") (pintype "passive"))
      (node (ref "R54") (pin "2") (pinfunction "2_2") (pintype "passive"))
      (node (ref "R57") (pin "2") (pinfunction "2_2") (pintype "passive"))
      (node (ref "R58") (pin "2") (pinfunction "2_2") (pintype "passive"))
      (node (ref "R59") (pin "2") (pinfunction "2_2") (pintype "passive"))
      (node (ref "R70") (pin "2") (pinfunction "2_2") (pintype "passive"))
      (node (ref "R71") (pin "2") (pinfunction "2_2") (pintype "passive"))
      (node (ref "R72") (pin "2") (pinfunction "2_2") (pintype "passive"))
      (node (ref "SD") (pin "4") (pinfunction "VDD_4") (pintype "bidirectional"))
      (node (ref "U4") (pin "5") (pinfunction "VOUT_5") (pintype "bidirectional"))
      (node (ref "U6") (pin "2") (pinfunction "3V3_2") (pintype "bidirectional"))
      (node (ref "U7") (pin "10") (pinfunction "V3_10") (pintype "bidirectional"))
      (node (ref "U7") (pin "7") (pinfunction "VCC_7") (pintype "bidirectional"))
    )
    (net (code "2") (name "/ANT") (class "Default")
      (node (ref "C42") (pin "2") (pinfunction "2_2") (pintype "passive"))
      (node (ref "R39") (pin "1") (pinfunction "1_1") (pintype "passive"))
      (node (ref "U5") (pin "60") (pinfunction "RF_ANT_60") (pintype "bidirectional"))
    )
    (net (code "3") (name "/BOOT") (class "Default")
      (node (ref "BOOT") (pin "2") (pinfunction "2_2") (pintype "passive"))
      (node (ref "U5") (pin "6") (pinfunction "USB_BOOT_6") (pintype "bidirectional"))
    )
    (net (code "4") (name "/DTR") (class "Default")
      (node (ref "Q11") (pin "2") (pinfunction "E_2") (pintype "passive"))
      (node (ref "R63") (pin "2") (pinfunction "2_2") (pintype "passive"))
      (node (ref "U7") (pin "4") (pinfunction "DTR#_4") (pintype "bidirectional"))
    )
    (net (code "5") (name "/EAR_N") (class "Default")
      (node (ref "FB2") (pin "2") (pinfunction "2_2") (pintype "passive"))
      (node (ref "U5") (pin "41") (pinfunction "EAR_N_41") (pintype "bidirectional"))
    )
    (net (code "6") (name "/EAR_P") (class "Default")
      (node (ref "FB1") (pin "1") (pinfunction "1_1") (pintype "passive"))
      (node (ref "U5") (pin "40") (pinfunction "EAR_P_40") (pintype "bidirectional"))
    )
    (net (code "7") (name "/GNSS_PWR_EN") (class "Default")
      (node (ref "U5") (pin "20") (pinfunction "MK_IN_3_20") (pintype "bidirectional"))
      (node (ref "U5") (pin "98") (pinfunction "NC_98") (pintype "bidirectional"))
    )
    (net (code "8") (name "/IO0") (class "Default")
      (node (ref "FLASH") (pin "2") (pinfunction "2_2") (pintype "passive"))
      (node (ref "Q11") (pin "3") (pinfunction "C_3") (pintype "passive"))
      (node (ref "R59") (pin "1") (pinfunction "1_1") (pintype "passive"))
      (node (ref "U6") (pin "27") (pinfunction "IO0_27") (pintype "bidirectional"))
    )
    (net (code "9") (name "/IO1") (class "Default")
      (node (ref "J2") (pin "1") (pinfunction "1_1") (pintype "bidirectional"))
      (node (ref "U6") (pin "39") (pinfunction "IO1_39") (pintype "bidirectional"))
    )
    (net (code "10") (name "/IO2") (class "Default")
      (node (ref "J2") (pin "2") (pinfunction "2_2") (pintype "bidirectional"))
      (node (ref "U6") (pin "38") (pinfunction "IO2_38") (pintype "bidirectional"))
    )
    (net (code "11") (name "/IO3") (class "Default")
      (node (ref "C1") (pin "1") (pinfunction "1_1") (pintype "passive"))
      (node (ref "J5") (pin "10") (pinfunction "10_10") (pintype "bidirectional"))
      (node (ref "R1") (pin "1") (pinfunction "1_1") (pintype "passive"))
      (node (ref "R2") (pin "2") (pinfunction "2_2") (pintype "passive"))
      (node (ref "U6") (pin "15") (pinfunction "IO3_15") (pintype "bidirectional"))
    )
    (net (code "12") (name "/IO4") (class "Default")
      (node (ref "R35") (pin "2") (pinfunction "2_2") (pintype "passive"))
      (node (ref "U6") (pin "4") (pinfunction "IO4_4") (pintype "bidirectional"))
    )
    (net (code "13") (name "/IO5") (class "Default")
      (node (ref "R31") (pin "2") (pinfunction "2_2") (pintype "passive"))
      (node (ref "U6") (pin "5") (pinfunction "IO5_5") (pintype "bidirectional"))
    )
    (net (code "14") (name "/IO6") (class "Default")
      (node (ref "Q8") (pin "3") (pinfunction "D_3") (pintype "passive"))
      (node (ref "R47") (pin "1") (pinfunction "1_1") (pintype "passive"))
      (node (ref "U6") (pin "6") (pinfunction "IO6_6") (pintype "bidirectional"))
    )
    (net (code "15") (name "/IO7") (class "Default")
      (node (ref "Q9") (pin "3") (pinfunction "D_3") (pintype "passive"))
      (node (ref "R49") (pin "1") (pinfunction "1_1") (pintype "passive"))
      (node (ref "U6") (pin "7") (pinfunction "IO7_7") (pintype "bidirectional"))
    )
    (net (code "16") (name "/IO8") (class "Default")
      (node (ref "J5") (pin "9") (pinfunction "9_9") (pintype "bidirectional"))
      (node (ref "U6") (pin "12") (pinfunction "IO8_12") (pintype "bidirectional"))
    )
    (net (code "17") (name "/IO9") (class "Default")
      (node (ref "J5") (pin "3") (pinfunction "3_3") (pintype "bidirectional"))
      (node (ref "U6") (pin "17") (pinfunction "IO9_17") (pintype "bidirectional"))
    )
    (net (code "18") (name "/IO10") (class "Default")
      (node (ref "R73") (pin "1") (pinfunction "1_1") (pintype "passive"))
      (node (ref "U6") (pin "18") (pinfunction "IO10_18") (pintype "bidirectional"))
    )
    (net (code "19") (name "/IO11{slash}MOSI") (class "Default")
      (node (ref "D4") (pin "3") (pinfunction "C2_3") (pintype "passive"))
      (node (ref "R4") (pin "1") (pinfunction "1_1") (pintype "passive"))
      (node (ref "SD") (pin "3") (pinfunction "DI_3") (pintype "bidirectional"))
      (node (ref "U6") (pin "19") (pinfunction "IO11_19") (pintype "bidirectional"))
    )
    (net (code "20") (name "/IO12{slash}SCLK") (class "Default")
      (node (ref "D4") (pin "5") (pinfunction "C4_5") (pintype "passive"))
      (node (ref "R3") (pin "1") (pinfunction "1_1") (pintype "passive"))
      (node (ref "SD") (pin "5") (pinfunction "SCLK_5") (pintype "bidirectional"))
      (node (ref "U6") (pin "20") (pinfunction "IO12_20") (pintype "bidirectional"))
    )
    (net (code "21") (name "/IO13{slash}MISO") (class "Default")
      (node (ref "D4") (pin "6") (pinfunction "C5_6") (pintype "passive"))
      (node (ref "R19") (pin "1") (pinfunction "1_1") (pintype "passive"))
      (node (ref "SD") (pin "7") (pinfunction "DO_7") (pintype "bidirectional"))
      (node (ref "U6") (pin "21") (pinfunction "IO13_21") (pintype "bidirectional"))
    )
    (net (code "22") (name "/IO14") (class "Default")
      (node (ref "J5") (pin "2") (pinfunction "2_2") (pintype "bidirectional"))
      (node (ref "U6") (pin "22") (pinfunction "IO14_22") (pintype "bidirectional"))
    )
    (net (code "23") (name "/IO15") (class "Default")
      (node (ref "J5") (pin "5") (pinfunction "5_5") (pintype "bidirectional"))
      (node (ref "U6") (pin "8") (pinfunction "IO15_8") (pintype "bidirectional"))
    )
    (net (code "24") (name "/IO16") (class "Default")
      (node (ref "J5") (pin "6") (pinfunction "6_6") (pintype "bidirectional"))
      (node (ref "U6") (pin "9") (pinfunction "IO16_9") (pintype "bidirectional"))
    )
    (net (code "25") (name "/IO17{slash}I2C_SDA") (class "Default")
      (node (ref "J5") (pin "7") (pinfunction "7_7") (pintype "bidirectional"))
      (node (ref "R58") (pin "1") (pinfunction "1_1") (pintype "passive"))
      (node (ref "U6") (pin "10") (pinfunction "IO17_10") (pintype "bidirectional"))
    )
    (net (code "26") (name "/IO18{slash}I2C_SCL") (class "Default")
      (node (ref "J5") (pin "8") (pinfunction "8_8") (pintype "bidirectional"))
      (node (ref "R57") (pin "1") (pinfunction "1_1") (pintype "passive"))
      (node (ref "U6") (pin "11") (pinfunction "IO18_11") (pintype "bidirectional"))
    )
    (net (code "27") (name "/IO19") (class "Default")
      (node (ref "R55") (pin "2") (pinfunction "2_2") (pintype "passive"))
      (node (ref "U6") (pin "13") (pinfunction "IO19_13") (pintype "bidirectional"))
    )
    (net (code "28") (name "/IO20") (class "Default")
      (node (ref "R56") (pin "2") (pinfunction "2_2") (pintype "passive"))
      (node (ref "U6") (pin "14") (pinfunction "IO20_14") (pintype "bidirectional"))
    )
    (net (code "29") (name "/IO21") (class "Default")
      (node (ref "U6") (pin "23") (pinfunction "IO21_23") (pintype "bidirectional"))
    )
    (net (code "30") (name "/IO38") (class "Default")
      (node (ref "J2") (pin "9") (pinfunction "9_9") (pintype "bidirectional"))
      (node (ref "U6") (pin "31") (pinfunction "IO38_31") (pintype "bidirectional"))
    )
    (net (code "31") (name "/IO39") (class "Default")
      (node (ref "J2") (pin "8") (pinfunction "8_8") (pintype "bidirectional"))
      (node (ref "U6") (pin "32") (pinfunction "IO39_32") (pintype "bidirectional"))
    )
    (net (code "32") (name "/IO40") (class "Default")
      (node (ref "J2") (pin "7") (pinfunction "7_7") (pintype "bidirectional"))
      (node (ref "U6") (pin "33") (pinfunction "IO40_33") (pintype "bidirectional"))
    )
    (net (code "33") (name "/IO41") (class "Default")
      (node (ref "J2") (pin "6") (pinfunction "6_6") (pintype "bidirectional"))
      (node (ref "U6") (pin "34") (pinfunction "IO41_34") (pintype "bidirectional"))
    )
    (net (code "34") (name "/IO42") (class "Default")
      (node (ref "J2") (pin "5") (pinfunction "5_5") (pintype "bidirectional"))
      (node (ref "U6") (pin "35") (pinfunction "IO42_35") (pintype "bidirectional"))
    )
    (net (code "35") (name "/IO45") (class "Default")
      (node (ref "J5") (pin "1") (pinfunction "1_1") (pintype "bidirectional"))
      (node (ref "U6") (pin "26") (pinfunction "IO45_26") (pintype "bidirectional"))
    )
    (net (code "36") (name "/IO46") (class "Default")
      (node (ref "J5") (pin "4") (pinfunction "4_4") (pintype "bidirectional"))
      (node (ref "U6") (pin "16") (pinfunction "IO46_16") (pintype "bidirectional"))
    )
    (net (code "37") (name "/IO47") (class "Default")
      (node (ref "Q5") (pin "3") (pinfunction "D_3") (pintype "passive"))
      (node (ref "R43") (pin "1") (pinfunction "1_1") (pintype "passive"))
      (node (ref "U6") (pin "24") (pinfunction "IO33_24") (pintype "bidirectional"))
    )
    (net (code "38") (name "/IO48") (class "Default")
      (node (ref "Q7") (pin "3") (pinfunction "D_3") (pintype "passive"))
      (node (ref "R45") (pin "1") (pinfunction "1_1") (pintype "passive"))
      (node (ref "U6") (pin "25") (pinfunction "IO34_25") (pintype "bidirectional"))
    )
    (net (code "39") (name "/LTE_DTR") (class "Default")
      (node (ref "Q9") (pin "2") (pinfunction "S_2") (pintype "passive"))
      (node (ref "R50") (pin "1") (pinfunction "1_1") (pintype "passive"))
      (node (ref "U5") (pin "3") (pinfunction "DTR_3") (pintype "bidirectional"))
    )
    (net (code "40") (name "/LTE_RI") (class "Default")
      (node (ref "Q8") (pin "2") (pinfunction "S_2") (pintype "passive"))
      (node (ref "R48") (pin "1") (pinfunction "1_1") (pintype "passive"))
      (node (ref "U5") (pin "4") (pinfunction "RI_4") (pintype "bidirectional"))
    )
    (net (code "41") (name "/LTE_RXD") (class "Default")
      (node (ref "Q7") (pin "2") (pinfunction "S_2") (pintype "passive"))
      (node (ref "R46") (pin "1") (pinfunction "1_1") (pintype "passive"))
      (node (ref "U5") (pin "10") (pinfunction "RXD_10") (pintype "bidirectional"))
    )
    (net (code "42") (name "/LTE_TXD") (class "Default")
      (node (ref "Q5") (pin "2") (pinfunction "S_2") (pintype "passive"))
      (node (ref "R44") (pin "1") (pinfunction "1_1") (pintype "passive"))
      (node (ref "U5") (pin "9") (pinfunction "TXD_9") (pintype "bidirectional"))
    )
    (net (code "43") (name "/MF_GNSS_RXD") (class "Default")
      (node (ref "R52") (pin "2") (pinfunction "2_2") (pintype "passive"))
      (node (ref "U5") (pin "49") (pinfunction "UART3_RXD_49") (pintype "bidirectional"))
    )
    (net (code "44") (name "/MF_GNSS_TXD") (class "Default")
      (node (ref "R53") (pin "2") (pinfunction "2_2") (pintype "passive"))
      (node (ref "U5") (pin "50") (pinfunction "UART3_TXD_50") (pintype "bidirectional"))
    )
    (net (code "45") (name "/MIC_N") (class "Default")
      (node (ref "FB4") (pin "1") (pinfunction "1_1") (pintype "passive"))
      (node (ref "R33") (pin "1") (pinfunction "1_1") (pintype "passive"))
      (node (ref "U5") (pin "43") (pinfunction "MIC_N_43") (pintype "bidirectional"))
    )
    (net (code "46") (name "/MIC_P") (class "Default")
      (node (ref "FB3") (pin "1") (pinfunction "1_1") (pintype "passive"))
      (node (ref "U5") (pin "42") (pinfunction "MIC_P_42") (pintype "bidirectional"))
    )
    (net (code "47") (name "/NETLED") (class "Default")
      (node (ref "R16") (pin "2") (pinfunction "2_2") (pintype "passive"))
      (node (ref "U5") (pin "52") (pinfunction "NETLIGHT_52") (pintype "bidirectional"))
    )
    (net (code "48") (name "/NRST") (class "Default")
      (node (ref "D12") (pin "-") (pinfunction "-_-") (pintype "passive"))
      (node (ref "Q1") (pin "3") (pinfunction "D_3") (pintype "passive"))
      (node (ref "U5") (pin "16") (pinfunction "RESET_16") (pintype "bidirectional"))
    )
    (net (code "49") (name "/PWRKEY") (class "Default")
      (node (ref "C27") (pin "2") (pinfunction "2_2") (pintype "passive"))
      (node (ref "PWK") (pin "2") (pinfunction "2_2") (pintype "passive"))
      (node (ref "Q3") (pin "3") (pinfunction "D_3") (pintype "passive"))
      (node (ref "U5") (pin "1") (pinfunction "PWRKEY_1") (pintype "bidirectional"))
    )
    (net (code "50") (name "/RESET") (class "Default")
      (node (ref "C39") (pin "1") (pinfunction "1_1") (pintype "passive"))
      (node (ref "Q10") (pin "3") (pinfunction "C_3") (pintype "passive"))
      (node (ref "R54") (pin "1") (pinfunction "1_1") (pintype "passive"))
      (node (ref "RST") (pin "2") (pinfunction "2_2") (pintype "passive"))
      (node (ref "U6") (pin "3") (pinfunction "EN_3") (pintype "bidirectional"))
    )
    (net (code "51") (name "/RTS") (class "Default")
      (node (ref "Q10") (pin "2") (pinfunction "E_2") (pintype "passive"))
      (node (ref "R62") (pin "2") (pinfunction "2_2") (pintype "passive"))
      (node (ref "U7") (pin "6") (pinfunction "RTS#_6") (pintype "bidirectional"))
    )
    (net (code "52") (name "/RXD{slash}IO44") (class "Default")
      (node (ref "J2") (pin "4") (pinfunction "4_4") (pintype "bidirectional"))
      (node (ref "R68") (pin "1") (pinfunction "1_1") (pintype "passive"))
      (node (ref "U6") (pin "36") (pinfunction "RXD0_36") (pintype "bidirectional"))
    )
    (net (code "53") (name "/SD_CS") (class "Default")
      (node (ref "D4") (pin "1") (pinfunction "C1_1") (pintype "passive"))
      (node (ref "R71") (pin "1") (pinfunction "1_1") (pintype "passive"))
      (node (ref "R73") (pin "2") (pinfunction "2_2") (pintype "passive"))
      (node (ref "SD") (pin "2") (pinfunction "CS_2") (pintype "bidirectional"))
    )
    (net (code "54") (name "/SIM_CLK") (class "Default")
      (node (ref "C35") (pin "2") (pinfunction "2_2") (pintype "passive"))
      (node (ref "D10") (pin "4") (pinfunction "C3_4") (pintype "passive"))
      (node (ref "R23") (pin "2") (pinfunction "2_2") (pintype "passive"))
      (node (ref "SIM") (pin "3") (pinfunction "CLK_3") (pintype "bidirectional"))
    )
    (net (code "55") (name "/SIM_DATA") (class "Default")
      (node (ref "C36") (pin "2") (pinfunction "2_2") (pintype "passive"))
      (node (ref "D10") (pin "3") (pinfunction "C2_3") (pintype "passive"))
      (node (ref "R22") (pin "2") (pinfunction "2_2") (pintype "passive"))
      (node (ref "SIM") (pin "7") (pinfunction "I/O_7") (pintype "bidirectional"))
    )
    (net (code "56") (name "/SIM_RST") (class "Default")
      (node (ref "C34") (pin "2") (pinfunction "2_2") (pintype "passive"))
      (node (ref "D10") (pin "5") (pinfunction "C4_5") (pintype "passive"))
      (node (ref "R24") (pin "2") (pinfunction "2_2") (pintype "passive"))
      (node (ref "SIM") (pin "2") (pinfunction "RST_2") (pintype "bidirectional"))
    )
    (net (code "57") (name "/SIM_VDD") (class "Default")
      (node (ref "C21") (pin "2") (pinfunction "2_2") (pintype "passive"))
      (node (ref "C52") (pin "2") (pinfunction "2_2") (pintype "passive"))
      (node (ref "D10") (pin "6") (pinfunction "C5_6") (pintype "passive"))
      (node (ref "SIM") (pin "1") (pinfunction "VCC_1") (pintype "bidirectional"))
      (node (ref "U5") (pin "30") (pinfunction "USIM1_VDD_30") (pintype "bidirectional"))
    )
    (net (code "58") (name "/STATUS") (class "Default")
      (node (ref "R41") (pin "2") (pinfunction "2_2") (pintype "passive"))
      (node (ref "U5") (pin "66") (pinfunction "STATUS_66") (pintype "bidirectional"))
    )
    (net (code "59") (name "/TXD{slash}IO43") (class "Default")
      (node (ref "J2") (pin "3") (pinfunction "3_3") (pintype "bidirectional"))
      (node (ref "R69") (pin "1") (pinfunction "1_1") (pintype "passive"))
      (node (ref "U6") (pin "37") (pinfunction "TXD0_37") (pintype "bidirectional"))
    )
    (net (code "60") (name "/UART_LOG_RX") (class "Default")
      (node (ref "RX") (pin "T") (pinfunction "T_T") (pintype "bidirectional"))
      (node (ref "U5") (pin "22") (pinfunction "UART_LOG_RX_22") (pintype "bidirectional"))
    )
    (net (code "61") (name "/UART_LOG_TX") (class "Default")
      (node (ref "TX") (pin "T") (pinfunction "T_T") (pintype "bidirectional"))
      (node (ref "U5") (pin "23") (pinfunction "UART_LOG_TX_23") (pintype "bidirectional"))
    )
    (net (code "62") (name "/USB_D+") (class "Default")
      (node (ref "R56") (pin "1") (pinfunction "1_1") (pintype "passive"))
      (node (ref "USB-NATIVE") (pin "A6") (pinfunction "D+_A6") (pintype "bidirectional"))
      (node (ref "USB-NATIVE") (pin "B6") (pinfunction "D+_B6") (pintype "bidirectional"))
    )
    (net (code "63") (name "/USB_D-") (class "Default")
      (node (ref "R55") (pin "1") (pinfunction "1_1") (pintype "passive"))
      (node (ref "USB-NATIVE") (pin "A7") (pinfunction "D-_A7") (pintype "bidirectional"))
      (node (ref "USB-NATIVE") (pin "B7") (pinfunction "D-_B7") (pintype "bidirectional"))
    )
    (net (code "64") (name "/USB_DN") (class "Default")
      (node (ref "R29") (pin "1") (pinfunction "1_1") (pintype "passive"))
      (node (ref "U5") (pin "28") (pinfunction "USB_DM_28") (pintype "bidirectional"))
    )
    (net (code "65") (name "/USB_DP") (class "Default")
      (node (ref "R28") (pin "1") (pinfunction "1_1") (pintype "passive"))
      (node (ref "U5") (pin "27") (pinfunction "USB_DP_27") (pintype "bidirectional"))
    )
    (net (code "66") (name "/VBAT-") (class "Default")
      (node (ref "BAT") (pin "1") (pinfunction "1_1") (pintype "bidirectional"))
      (node (ref "C25") (pin "1") (pinfunction "1_1") (pintype "passive"))
      (node (ref "J3") (pin "2") (pinfunction "2_2") (pintype "passive"))
      (node (ref "R10") (pin "2") (pinfunction "2_2") (pintype "passive"))
      (node (ref "U1") (pin "3") (pinfunction "S2_3") (pintype "bidirectional"))
      (node (ref "U1") (pin "6") (pinfunction "VSS_6") (pintype "bidirectional"))
    )
    (net (code "67") (name "/VBAT_ADC") (class "Default")
      (node (ref "C2") (pin "1") (pinfunction "1_1") (pintype "passive"))
      (node (ref "R5") (pin "1") (pinfunction "1_1") (pintype "passive"))
      (node (ref "R7") (pin "2") (pinfunction "2_2") (pintype "passive"))
      (node (ref "U5") (pin "51") (pinfunction "VBAT_ADC_51") (pintype "bidirectional"))
    )
    (net (code "68") (name "/VBAT_IN") (class "Default")
      (node (ref "C29") (pin "1") (pinfunction "1_1") (pintype "passive"))
      (node (ref "C38") (pin "1") (pinfunction "1_1") (pintype "passive"))
      (node (ref "D2") (pin "A") (pinfunction "A_A") (pintype "passive"))
      (node (ref "Q2") (pin "3") (pinfunction "D_3") (pintype "passive"))
      (node (ref "R5") (pin "2") (pinfunction "2_2") (pintype "passive"))
      (node (ref "SW1") (pin "CH1A") (pinfunction "CH1A_CH1A") (pintype "bidirectional"))
    )
    (net (code "69") (name "/VIN") (class "Default")
      (node (ref "C10") (pin "2") (pinfunction "2_2") (pintype "passive"))
      (node (ref "C17") (pin "2") (pinfunction "2_2") (pintype "passive"))
      (node (ref "D1") (pin "C") (pinfunction "C_C") (pintype "passive"))
      (node (ref "D2") (pin "C") (pinfunction "C_C") (pintype "passive"))
      (node (ref "Q2") (pin "2") (pinfunction "S_2") (pintype "passive"))
      (node (ref "R6") (pin "2") (pinfunction "2_2") (pintype "passive"))
      (node (ref "U4") (pin "1") (pinfunction "VIN_1") (pintype "bidirectional"))
      (node (ref "U4") (pin "3") (pinfunction "EN_3") (pintype "bidirectional"))
    )
    (net (code "70") (name "/VSYS") (class "Default")
      (node (ref "D11") (pin "A") (pinfunction "A_A") (pintype "passive"))
      (node (ref "Q2") (pin "1") (pinfunction "G_1") (pintype "passive"))
      (node (ref "R15") (pin "1") (pinfunction "1_1") (pintype "passive"))
      (node (ref "SW1") (pin "CH2A") (pinfunction "CH2A_CH2A") (pintype "bidirectional"))
    )
    (net (code "71") (name "/VUSB") (class "Default")
      (node (ref "C12") (pin "1") (pinfunction "1_1") (pintype "passive"))
      (node (ref "C15") (pin "1") (pinfunction "1_1") (pintype "passive"))
      (node (ref "D5") (pin "A") (pinfunction "A_A") (pintype "passive"))
      (node (ref "U5") (pin "24") (pinfunction "VBUS_24") (pintype "bidirectional"))
      (node (ref "USB-LTE") (pin "VBUS1") (pinfunction "VBUS_VBUS1") (pintype "bidirectional"))
      (node (ref "USB-LTE") (pin "VBUS2") (pinfunction "VBUS_VBUS2") (pintype "bidirectional"))
    )
    (net (code "72") (name "1.8V") (class "Default")
      (node (ref "1V8") (pin "T") (pinfunction "T_T") (pintype "bidirectional"))
      (node (ref "C32") (pin "2") (pinfunction "2_2") (pintype "passive"))
      (node (ref "C33") (pin "2") (pinfunction "2_2") (pintype "passive"))
      (node (ref "D6") (pin "+") (pinfunction "+_+") (pintype "passive"))
      (node (ref "Q5") (pin "1") (pinfunction "G_1") (pintype "passive"))
      (node (ref "Q7") (pin "1") (pinfunction "G_1") (pintype "passive"))
      (node (ref "Q8") (pin "1") (pinfunction "G_1") (pintype "passive"))
      (node (ref "Q9") (pin "1") (pinfunction "G_1") (pintype "passive"))
      (node (ref "R44") (pin "2") (pinfunction "2_2") (pintype "passive"))
      (node (ref "R46") (pin "2") (pinfunction "2_2") (pintype "passive"))
      (node (ref "R48") (pin "2") (pinfunction "2_2") (pintype "passive"))
      (node (ref "R50") (pin "2") (pinfunction "2_2") (pintype "passive"))
      (node (ref "U5") (pin "15") (pinfunction "VDD_EXT_15") (pintype "bidirectional"))
      (node (ref "U5") (pin "97") (pinfunction "NC_97") (pintype "bidirectional"))
    )
    (net (code "73") (name "5V") (class "Default")
      (node (ref "C13") (pin "1") (pinfunction "1_1") (pintype "passive"))
      (node (ref "CHRG") (pin "A") (pinfunction "A_A") (pintype "passive"))
      (node (ref "D14") (pin "-") (pinfunction "-_-") (pintype "passive"))
      (node (ref "D3") (pin "C") (pinfunction "C_C") (pintype "passive"))
      (node (ref "D5") (pin "C") (pinfunction "C_C") (pintype "passive"))
      (node (ref "D9") (pin "-") (pinfunction "-_-") (pintype "passive"))
      (node (ref "DONE") (pin "A") (pinfunction "A_A") (pintype "passive"))
      (node (ref "J2") (pin "13") (pinfunction "13_13") (pintype "bidirectional"))
      (node (ref "SW1") (pin "COM2") (pinfunction "COM2_COM2") (pintype "bidirectional"))
      (node (ref "U3") (pin "4") (pinfunction "VIN_4") (pintype "bidirectional"))
      (node (ref "U3") (pin "8") (pinfunction "CE_8") (pintype "bidirectional"))
      (node (ref "USB-NATIVE") (pin "VBUS1") (pinfunction "VBUS_VBUS1") (pintype "bidirectional"))
      (node (ref "USB-NATIVE") (pin "VBUS2") (pinfunction "VBUS_VBUS2") (pintype "bidirectional"))
    )
    (net (code "74") (name "AGND") (class "Default")
      (node (ref "C14") (pin "1") (pinfunction "1_1") (pintype "passive"))
      (node (ref "C16") (pin "1") (pinfunction "1_1") (pintype "passive"))
      (node (ref "C20") (pin "1") (pinfunction "1_1") (pintype "passive"))
      (node (ref "C4") (pin "1") (pinfunction "1_1") (pintype "passive"))
      (node (ref "C56") (pin "2") (pinfunction "2_2") (pintype "passive"))
      (node (ref "C57") (pin "2") (pinfunction "2_2") (pintype "passive"))
      (node (ref "C79") (pin "1") (pinfunction "1_1") (pintype "passive"))
      (node (ref "C80") (pin "2") (pinfunction "2_2") (pintype "passive"))
      (node (ref "C82") (pin "2") (pinfunction "2_2") (pintype "passive"))
      (node (ref "C83") (pin "1") (pinfunction "1_1") (pintype "passive"))
      (node (ref "FB5") (pin "1") (pinfunction "1_1") (pintype "passive"))
      (node (ref "R33") (pin "2") (pinfunction "2_2") (pintype "passive"))
    )
    (net (code "75") (name "D+") (class "Default")
      (node (ref "U7") (pin "1") (pinfunction "UD+_1") (pintype "bidirectional"))
      (node (ref "USB-TTL") (pin "A6") (pinfunction "D+_A6") (pintype "bidirectional"))
      (node (ref "USB-TTL") (pin "B6") (pinfunction "D+_B6") (pintype "bidirectional"))
    )
    (net (code "76") (name "D-") (class "Default")
      (node (ref "U7") (pin "2") (pinfunction "UD-_2") (pintype "bidirectional"))
      (node (ref "USB-TTL") (pin "A7") (pinfunction "D-_A7") (pintype "bidirectional"))
      (node (ref "USB-TTL") (pin "B7") (pinfunction "D-_B7") (pintype "bidirectional"))
    )
    (net (code "77") (name "GND") (class "Default")
      (node (ref "C1") (pin "2") (pinfunction "2_2") (pintype "passive"))
      (node (ref "C10") (pin "1") (pinfunction "1_1") (pintype "passive"))
      (node (ref "C11") (pin "1") (pinfunction "1_1") (pintype "passive"))
      (node (ref "C12") (pin "2") (pinfunction "2_2") (pintype "passive"))
      (node (ref "C13") (pin "2") (pinfunction "2_2") (pintype "passive"))
      (node (ref "C15") (pin "2") (pinfunction "2_2") (pintype "passive"))
      (node (ref "C17") (pin "1") (pinfunction "1_1") (pintype "passive"))
      (node (ref "C18") (pin "1") (pinfunction "1_1") (pintype "passive"))
      (node (ref "C19") (pin "1") (pinfunction "1_1") (pintype "passive"))
      (node (ref "C2") (pin "2") (pinfunction "2_2") (pintype "passive"))
      (node (ref "C21") (pin "1") (pinfunction "1_1") (pintype "passive"))
      (node (ref "C22") (pin "1") (pinfunction "1_1") (pintype "passive"))
      (node (ref "C23") (pin "1") (pinfunction "1_1") (pintype "passive"))
      (node (ref "C24") (pin "1") (pinfunction "1_1") (pintype "passive"))
      (node (ref "C26") (pin "C") (pinfunction "-_C") (pintype "passive"))
      (node (ref "C27") (pin "1") (pinfunction "1_1") (pintype "passive"))
      (node (ref "C29") (pin "2") (pinfunction "2_2") (pintype "passive"))
      (node (ref "C30") (pin "1") (pinfunction "1_1") (pintype "passive"))
      (node (ref "C31") (pin "1") (pinfunction "1_1") (pintype "passive"))
      (node (ref "C32") (pin "1") (pinfunction "1_1") (pintype "passive"))
      (node (ref "C33") (pin "1") (pinfunction "1_1") (pintype "passive"))
      (node (ref "C34") (pin "1") (pinfunction "1_1") (pintype "passive"))
      (node (ref "C35") (pin "1") (pinfunction "1_1") (pintype "passive"))
      (node (ref "C36") (pin "1") (pinfunction "1_1") (pintype "passive"))
      (node (ref "C38") (pin "2") (pinfunction "2_2") (pintype "passive"))
      (node (ref "C39") (pin "2") (pinfunction "2_2") (pintype "passive"))
      (node (ref "C40") (pin "1") (pinfunction "1_1") (pintype "passive"))
      (node (ref "C42") (pin "1") (pinfunction "1_1") (pintype "passive"))
      (node (ref "C43") (pin "1") (pinfunction "1_1") (pintype "passive"))
      (node (ref "C44") (pin "2") (pinfunction "2_2") (pintype "passive"))
      (node (ref "C46") (pin "1") (pinfunction "1_1") (pintype "passive"))
      (node (ref "C47") (pin "1") (pinfunction "1_1") (pintype "passive"))
      (node (ref "C48") (pin "C") (pinfunction "-_C") (pintype "passive"))
      (node (ref "C49") (pin "1") (pinfunction "1_1") (pintype "passive"))
      (node (ref "C5") (pin "1") (pinfunction "1_1") (pintype "passive"))
      (node (ref "C50") (pin "1") (pinfunction "1_1") (pintype "passive"))
      (node (ref "C51") (pin "1") (pinfunction "1_1") (pintype "passive"))
      (node (ref "C52") (pin "1") (pinfunction "1_1") (pintype "passive"))
      (node (ref "C53") (pin "1") (pinfunction "1_1") (pintype "passive"))
      (node (ref "C54") (pin "1") (pinfunction "1_1") (pintype "passive"))
      (node (ref "C58") (pin "1") (pinfunction "1_1") (pintype "passive"))
      (node (ref "C59") (pin "1") (pinfunction "1_1") (pintype "passive"))
      (node (ref "C6") (pin "1") (pinfunction "1_1") (pintype "passive"))
      (node (ref "C7") (pin "2") (pinfunction "2_2") (pintype "passive"))
      (node (ref "C8") (pin "2") (pinfunction "2_2") (pintype "passive"))
      (node (ref "D10") (pin "2") (pinfunction "A_2") (pintype "passive"))
      (node (ref "D12") (pin "+") (pinfunction "+_+") (pintype "passive"))
      (node (ref "D13") (pin "+") (pinfunction "+_+") (pintype "passive"))
      (node (ref "D14") (pin "+") (pinfunction "+_+") (pintype "passive"))
      (node (ref "D4") (pin "2") (pinfunction "A_2") (pintype "passive"))
      (node (ref "D7") (pin "+") (pinfunction "+_+") (pintype "passive"))
      (node (ref "D8") (pin "A") (pinfunction "A_A") (pintype "passive"))
      (node (ref "D9") (pin "+") (pinfunction "+_+") (pintype "passive"))
      (node (ref "FB5") (pin "2") (pinfunction "2_2") (pintype "passive"))
      (node (ref "FLASH") (pin "1") (pinfunction "1_1") (pintype "passive"))
      (node (ref "GND") (pin "T") (pinfunction "T_T") (pintype "bidirectional"))
      (node (ref "GPS") (pin "GND1") (pinfunction "GND1_GND1") (pintype "bidirectional"))
      (node (ref "GPS") (pin "GND2") (pinfunction "GND2_GND2") (pintype "bidirectional"))
      (node (ref "GPS") (pin "GND3") (pinfunction "GND3_GND3") (pintype "bidirectional"))
      (node (ref "J1") (pin "2") (pinfunction "2_2") (pintype "bidirectional"))
      (node (ref "J2") (pin "10") (pinfunction "10_10") (pintype "bidirectional"))
      (node (ref "J2") (pin "12") (pinfunction "12_12") (pintype "bidirectional"))
      (node (ref "J5") (pin "12") (pinfunction "12_12") (pintype "bidirectional"))
      (node (ref "LTE") (pin "GND1") (pinfunction "GND1_GND1") (pintype "bidirectional"))
      (node (ref "LTE") (pin "GND2") (pinfunction "GND2_GND2") (pintype "bidirectional"))
      (node (ref "LTE") (pin "GND3") (pinfunction "GND3_GND3") (pintype "bidirectional"))
      (node (ref "PWK") (pin "1") (pinfunction "1_1") (pintype "passive"))
      (node (ref "Q1") (pin "2") (pinfunction "S_2") (pintype "passive"))
      (node (ref "Q3") (pin "2") (pinfunction "S_2") (pintype "passive"))
      (node (ref "Q4") (pin "2") (pinfunction "S_2") (pintype "passive"))
      (node (ref "Q6") (pin "2") (pinfunction "S_2") (pintype "passive"))
      (node (ref "R10") (pin "1") (pinfunction "1_1") (pintype "passive"))
      (node (ref "R12") (pin "2") (pinfunction "2_2") (pintype "passive"))
      (node (ref "R14") (pin "1") (pinfunction "1_1") (pintype "passive"))
      (node (ref "R15") (pin "2") (pinfunction "2_2") (pintype "passive"))
      (node (ref "R2") (pin "1") (pinfunction "1_1") (pintype "passive"))
      (node (ref "R25") (pin "2") (pinfunction "2_2") (pintype "passive"))
      (node (ref "R26") (pin "1") (pinfunction "1_1") (pintype "passive"))
      (node (ref "R27") (pin "1") (pinfunction "1_1") (pintype "passive"))
      (node (ref "R30") (pin "2") (pinfunction "2_2") (pintype "passive"))
      (node (ref "R32") (pin "1") (pinfunction "1_1") (pintype "passive"))
      (node (ref "R34") (pin "2") (pinfunction "2_2") (pintype "passive"))
      (node (ref "R36") (pin "1") (pinfunction "1_1") (pintype "passive"))
      (node (ref "R42") (pin "1") (pinfunction "1_1") (pintype "passive"))
      (node (ref "R60") (pin "1") (pinfunction "1_1") (pintype "passive"))
      (node (ref "R61") (pin "1") (pinfunction "1_1") (pintype "passive"))
      (node (ref "R64") (pin "1") (pinfunction "1_1") (pintype "passive"))
      (node (ref "R67") (pin "1") (pinfunction "1_1") (pintype "passive"))
      (node (ref "R7") (pin "1") (pinfunction "1_1") (pintype "passive"))
      (node (ref "R8") (pin "1") (pinfunction "1_1") (pintype "passive"))
      (node (ref "RST") (pin "1") (pinfunction "1_1") (pintype "passive"))
      (node (ref "SD") (pin "6") (pinfunction "VSS_6") (pintype "bidirectional"))
      (node (ref "SD") (pin "G1") (pinfunction "G1_G1") (pintype "bidirectional"))
      (node (ref "SD") (pin "G2") (pinfunction "G2_G2") (pintype "bidirectional"))
      (node (ref "SD") (pin "G3") (pinfunction "G3_G3") (pintype "bidirectional"))
      (node (ref "SD") (pin "G4") (pinfunction "G4_G4") (pintype "bidirectional"))
      (node (ref "SIM") (pin "5") (pinfunction "GND_5") (pintype "bidirectional"))
      (node (ref "U1") (pin "2") (pinfunction "S1_2") (pintype "bidirectional"))
      (node (ref "U3") (pin "1") (pinfunction "TEMP_1") (pintype "bidirectional"))
      (node (ref "U3") (pin "3") (pinfunction "GND_3") (pintype "bidirectional"))
      (node (ref "U3") (pin "9") (pinfunction "GND_9") (pintype "bidirectional"))
      (node (ref "U4") (pin "2") (pinfunction "GND_2") (pintype "bidirectional"))
      (node (ref "U5") (pin "17") (pinfunction "GND_17") (pintype "bidirectional"))
      (node (ref "U5") (pin "18") (pinfunction "GND_18") (pintype "bidirectional"))
      (node (ref "U5") (pin "2") (pinfunction "GND_2") (pintype "bidirectional"))
      (node (ref "U5") (pin "29") (pinfunction "GND_29") (pintype "bidirectional"))
      (node (ref "U5") (pin "39") (pinfunction "GND_39") (pintype "bidirectional"))
      (node (ref "U5") (pin "45") (pinfunction "GND_45") (pintype "bidirectional"))
      (node (ref "U5") (pin "46") (pinfunction "GND_46") (pintype "bidirectional"))
      (node (ref "U5") (pin "54") (pinfunction "GND_54") (pintype "bidirectional"))
      (node (ref "U5") (pin "58") (pinfunction "GND_58") (pintype "bidirectional"))
      (node (ref "U5") (pin "59") (pinfunction "GND_59") (pintype "bidirectional"))
      (node (ref "U5") (pin "61") (pinfunction "GND_61") (pintype "bidirectional"))
      (node (ref "U5") (pin "62") (pinfunction "GND_62") (pintype "bidirectional"))
      (node (ref "U5") (pin "63") (pinfunction "GND_63") (pintype "bidirectional"))
      (node (ref "U5") (pin "64") (pinfunction "GND_64") (pintype "bidirectional"))
      (node (ref "U5") (pin "65") (pinfunction "GND_65") (pintype "bidirectional"))
      (node (ref "U5") (pin "69") (pinfunction "GND_69") (pintype "bidirectional"))
      (node (ref "U5") (pin "70") (pinfunction "GND_70") (pintype "bidirectional"))
      (node (ref "U5") (pin "71") (pinfunction "GND_71") (pintype "bidirectional"))
      (node (ref "U5") (pin "72") (pinfunction "GND_72") (pintype "bidirectional"))
      (node (ref "U5") (pin "73") (pinfunction "GND_73") (pintype "bidirectional"))
      (node (ref "U5") (pin "74") (pinfunction "GND_74") (pintype "bidirectional"))
      (node (ref "U5") (pin "75") (pinfunction "GND_75") (pintype "bidirectional"))
      (node (ref "U5") (pin "76") (pinfunction "GND_76") (pintype "bidirectional"))
      (node (ref "U5") (pin "77") (pinfunction "GND_77") (pintype "bidirectional"))
      (node (ref "U5") (pin "78") (pinfunction "GND_78") (pintype "bidirectional"))
      (node (ref "U5") (pin "79") (pinfunction "GND_79") (pintype "bidirectional"))
      (node (ref "U5") (pin "80") (pinfunction "GND_80") (pintype "bidirectional"))
      (node (ref "U5") (pin "81") (pinfunction "GND_81") (pintype "bidirectional"))
      (node (ref "U5") (pin "82") (pinfunction "GND_82") (pintype "bidirectional"))
      (node (ref "U5") (pin "83") (pinfunction "GND_83") (pintype "bidirectional"))
      (node (ref "U5") (pin "84") (pinfunction "GND_84") (pintype "bidirectional"))
      (node (ref "U5") (pin "85") (pinfunction "GND_85") (pintype "bidirectional"))
      (node (ref "U5") (pin "86") (pinfunction "GND_86") (pintype "bidirectional"))
      (node (ref "U5") (pin "87") (pinfunction "GND_87") (pintype "bidirectional"))
      (node (ref "U5") (pin "88") (pinfunction "GND_88") (pintype "bidirectional"))
      (node (ref "U5") (pin "89") (pinfunction "GND_89") (pintype "bidirectional"))
      (node (ref "U5") (pin "91") (pinfunction "GND_91") (pintype "bidirectional"))
      (node (ref "U5") (pin "92") (pinfunction "GND_92") (pintype "bidirectional"))
      (node (ref "U5") (pin "94") (pinfunction "GND_94") (pintype "bidirectional"))
      (node (ref "U6") (pin "1") (pinfunction "GND_1") (pintype "bidirectional"))
      (node (ref "U6") (pin "40") (pinfunction "GND_40") (pintype "bidirectional"))
      (node (ref "U6") (pin "41") (pinfunction "EPAD_41") (pintype "bidirectional"))
      (node (ref "U7") (pin "3") (pinfunction "GND_3") (pintype "bidirectional"))
      (node (ref "U7") (pin "EP") (pinfunction "EP_EP") (pintype "bidirectional"))
      (node (ref "USB-LTE") (pin "GND") (pinfunction "GND_GND") (pintype "bidirectional"))
      (node (ref "USB-LTE") (pin "GND2") (pinfunction "GND_GND2") (pintype "bidirectional"))
      (node (ref "USB-LTE") (pin "SHLD1") (pinfunction "SHLD_SHLD1") (pintype "bidirectional"))
      (node (ref "USB-LTE") (pin "SHLD2") (pinfunction "SHLD_SHLD2") (pintype "bidirectional"))
      (node (ref "USB-LTE") (pin "SHLD3") (pinfunction "SHLD_SHLD3") (pintype "bidirectional"))
      (node (ref "USB-LTE") (pin "SHLD4") (pinfunction "SHLD_SHLD4") (pintype "bidirectional"))
      (node (ref "USB-LTE") (pin "SHLD5") (pinfunction "SHLD_SHLD5") (pintype "bidirectional"))
      (node (ref "USB-LTE") (pin "SHLD6") (pinfunction "SHLD_SHLD6") (pintype "bidirectional"))
      (node (ref "USB-LTE") (pin "SHLD7") (pinfunction "SHLD_SHLD7") (pintype "bidirectional"))
      (node (ref "USB-LTE") (pin "SHLD8") (pinfunction "SHLD_SHLD8") (pintype "bidirectional"))
      (node (ref "USB-NATIVE") (pin "GND") (pinfunction "GND_GND") (pintype "bidirectional"))
      (node (ref "USB-NATIVE") (pin "GND2") (pinfunction "GND_GND2") (pintype "bidirectional"))
      (node (ref "USB-NATIVE") (pin "SHLD1") (pinfunction "SHLD_SHLD1") (pintype "bidirectional"))
      (node (ref "USB-NATIVE") (pin "SHLD2") (pinfunction "SHLD_SHLD2") (pintype "bidirectional"))
      (node (ref "USB-NATIVE") (pin "SHLD3") (pinfunction "SHLD_SHLD3") (pintype "bidirectional"))
      (node (ref "USB-NATIVE") (pin "SHLD4") (pinfunction "SHLD_SHLD4") (pintype "bidirectional"))
      (node (ref "USB-NATIVE") (pin "SHLD5") (pinfunction "SHLD_SHLD5") (pintype "bidirectional"))
      (node (ref "USB-NATIVE") (pin "SHLD6") (pinfunction "SHLD_SHLD6") (pintype "bidirectional"))
      (node (ref "USB-NATIVE") (pin "SHLD7") (pinfunction "SHLD_SHLD7") (pintype "bidirectional"))
      (node (ref "USB-NATIVE") (pin "SHLD8") (pinfunction "SHLD_SHLD8") (pintype "bidirectional"))
      (node (ref "USB-TTL") (pin "GND") (pinfunction "GND_GND") (pintype "bidirectional"))
      (node (ref "USB-TTL") (pin "GND2") (pinfunction "GND_GND2") (pintype "bidirectional"))
      (node (ref "USB-TTL") (pin "SHLD1") (pinfunction "SHLD_SHLD1") (pintype "bidirectional"))
      (node (ref "USB-TTL") (pin "SHLD2") (pinfunction "SHLD_SHLD2") (pintype "bidirectional"))
      (node (ref "USB-TTL") (pin "SHLD3") (pinfunction "SHLD_SHLD3") (pintype "bidirectional"))
      (node (ref "USB-TTL") (pin "SHLD4") (pinfunction "SHLD_SHLD4") (pintype "bidirectional"))
      (node (ref "USB-TTL") (pin "SHLD5") (pinfunction "SHLD_SHLD5") (pintype "bidirectional"))
      (node (ref "USB-TTL") (pin "SHLD6") (pinfunction "SHLD_SHLD6") (pintype "bidirectional"))
      (node (ref "USB-TTL") (pin "SHLD7") (pinfunction "SHLD_SHLD7") (pintype "bidirectional"))
      (node (ref "USB-TTL") (pin "SHLD8") (pinfunction "SHLD_SHLD8") (pintype "bidirectional"))
    )
    (net (code "78") (name "Net-(BOOT-Pad1)") (class "Default")
      (node (ref "BOOT") (pin "1") (pinfunction "1_1") (pintype "passive"))
      (node (ref "R34") (pin "1") (pinfunction "1_1") (pintype "passive"))
    )
    (net (code "79") (name "Net-(C14-Pad2)") (class "Default")
      (node (ref "C14") (pin "2") (pinfunction "2_2") (pintype "passive"))
      (node (ref "C4") (pin "2") (pinfunction "2_2") (pintype "passive"))
      (node (ref "C55") (pin "1") (pinfunction "1_1") (pintype "passive"))
      (node (ref "C9") (pin "1") (pinfunction "1_1") (pintype "passive"))
      (node (ref "FB4") (pin "2") (pinfunction "2_2") (pintype "passive"))
    )
    (net (code "80") (name "Net-(C16-Pad2)") (class "Default")
      (node (ref "C16") (pin "2") (pinfunction "2_2") (pintype "passive"))
      (node (ref "R21") (pin "1") (pinfunction "1_1") (pintype "passive"))
      (node (ref "R37") (pin "1") (pinfunction "1_1") (pintype "passive"))
      (node (ref "R9") (pin "1") (pinfunction "1_1") (pintype "passive"))
    )
    (net (code "81") (name "Net-(C20-Pad2)") (class "Default")
      (node (ref "C20") (pin "2") (pinfunction "2_2") (pintype "passive"))
      (node (ref "C55") (pin "2") (pinfunction "2_2") (pintype "passive"))
      (node (ref "C56") (pin "1") (pinfunction "1_1") (pintype "passive"))
      (node (ref "C57") (pin "1") (pinfunction "1_1") (pintype "passive"))
      (node (ref "C9") (pin "2") (pinfunction "2_2") (pintype "passive"))
      (node (ref "FB3") (pin "2") (pinfunction "2_2") (pintype "passive"))
      (node (ref "R51") (pin "2") (pinfunction "2_2") (pintype "passive"))
      (node (ref "R9") (pin "2") (pinfunction "2_2") (pintype "passive"))
    )
    (net (code "82") (name "Net-(C28-Pad1)") (class "Default")
      (node (ref "C28") (pin "1") (pinfunction "1_1") (pintype "passive"))
      (node (ref "C78") (pin "1") (pinfunction "1_1") (pintype "passive"))
      (node (ref "C79") (pin "2") (pinfunction "2_2") (pintype "passive"))
      (node (ref "C81") (pin "1") (pinfunction "1_1") (pintype "passive"))
      (node (ref "C83") (pin "2") (pinfunction "2_2") (pintype "passive"))
      (node (ref "R66") (pin "1") (pinfunction "1_1") (pintype "passive"))
    )
    (net (code "83") (name "Net-(C28-Pad2)") (class "Default")
      (node (ref "C28") (pin "2") (pinfunction "2_2") (pintype "passive"))
      (node (ref "EAR") (pin "4") (pinfunction "4_4") (pintype "bidirectional"))
    )
    (net (code "84") (name "Net-(C37-Pad1)") (class "Default")
      (node (ref "C37") (pin "1") (pinfunction "1_1") (pintype "passive"))
      (node (ref "C78") (pin "2") (pinfunction "2_2") (pintype "passive"))
      (node (ref "C80") (pin "1") (pinfunction "1_1") (pintype "passive"))
      (node (ref "C81") (pin "2") (pinfunction "2_2") (pintype "passive"))
      (node (ref "C82") (pin "1") (pinfunction "1_1") (pintype "passive"))
      (node (ref "R65") (pin "1") (pinfunction "1_1") (pintype "passive"))
    )
    (net (code "85") (name "Net-(C37-Pad2)") (class "Default")
      (node (ref "C37") (pin "2") (pinfunction "2_2") (pintype "passive"))
      (node (ref "EAR") (pin "3") (pinfunction "3_3") (pintype "bidirectional"))
    )
    (net (code "86") (name "Net-(C43-Pad2)") (class "Default")
      (node (ref "C43") (pin "2") (pinfunction "2_2") (pintype "passive"))
      (node (ref "R20") (pin "1") (pinfunction "1_1") (pintype "passive"))
      (node (ref "R39") (pin "2") (pinfunction "2_2") (pintype "passive"))
    )
    (net (code "87") (name "Net-(C44-Pad1)") (class "Default")
      (node (ref "C44") (pin "1") (pinfunction "1_1") (pintype "passive"))
      (node (ref "L1") (pin "1") (pinfunction "1_1") (pintype "passive"))
      (node (ref "R40") (pin "1") (pinfunction "1_1") (pintype "passive"))
    )
    (net (code "88") (name "Net-(C45-Pad1)") (class "Default")
      (node (ref "C45") (pin "1") (pinfunction "1_1") (pintype "passive"))
      (node (ref "GPS") (pin "D") (pinfunction "D_D") (pintype "bidirectional"))
      (node (ref "L1") (pin "2") (pinfunction "2_2") (pintype "passive"))
    )
    (net (code "89") (name "Net-(C45-Pad2)") (class "Default")
      (node (ref "C45") (pin "2") (pinfunction "2_2") (pintype "passive"))
      (node (ref "U5") (pin "90") (pinfunction "NC_90") (pintype "bidirectional"))
    )
    (net (code "90") (name "Net-(C58-Pad2)") (class "Default")
      (node (ref "C58") (pin "2") (pinfunction "2_2") (pintype "passive"))
      (node (ref "D6") (pin "-") (pinfunction "-_-") (pintype "passive"))
      (node (ref "U5") (pin "116") (pinfunction "NC_116") (pintype "bidirectional"))
    )
    (net (code "91") (name "Net-(CHRG-PadC)") (class "Default")
      (node (ref "CHRG") (pin "C") (pinfunction "C_C") (pintype "passive"))
      (node (ref "R13") (pin "1") (pinfunction "1_1") (pintype "passive"))
    )
    (net (code "92") (name "Net-(D1-PadA)") (class "Default")
      (node (ref "D1") (pin "A") (pinfunction "A_A") (pintype "passive"))
      (node (ref "D11") (pin "C") (pinfunction "C_C") (pintype "passive"))
    )
    (net (code "93") (name "Net-(D13-Pad-)") (class "Default")
      (node (ref "D13") (pin "-") (pinfunction "-_-") (pintype "passive"))
      (node (ref "LTE") (pin "D") (pinfunction "D_D") (pintype "bidirectional"))
      (node (ref "R20") (pin "2") (pinfunction "2_2") (pintype "passive"))
    )
    (net (code "94") (name "Net-(DONE-PadC)") (class "Default")
      (node (ref "DONE") (pin "C") (pinfunction "C_C") (pintype "passive"))
      (node (ref "R17") (pin "1") (pinfunction "1_1") (pintype "passive"))
    )
    (net (code "95") (name "Net-(EAR-Pad1)") (class "Default")
      (node (ref "EAR") (pin "1") (pinfunction "1_1") (pintype "bidirectional"))
      (node (ref "R30") (pin "1") (pinfunction "1_1") (pintype "passive"))
      (node (ref "R37") (pin "2") (pinfunction "2_2") (pintype "passive"))
    )
    (net (code "96") (name "Net-(EAR-Pad2)") (class "Default")
      (node (ref "EAR") (pin "2") (pinfunction "2_2") (pintype "bidirectional"))
      (node (ref "R21") (pin "2") (pinfunction "2_2") (pintype "passive"))
      (node (ref "R25") (pin "1") (pinfunction "1_1") (pintype "passive"))
    )
    (net (code "97") (name "Net-(FB1-Pad2)") (class "Default")
      (node (ref "FB1") (pin "2") (pinfunction "2_2") (pintype "passive"))
      (node (ref "R65") (pin "2") (pinfunction "2_2") (pintype "passive"))
    )
    (net (code "98") (name "Net-(FB2-Pad1)") (class "Default")
      (node (ref "FB2") (pin "1") (pinfunction "1_1") (pintype "passive"))
      (node (ref "R66") (pin "2") (pinfunction "2_2") (pintype "passive"))
    )
    (net (code "99") (name "Net-(NET-PadA)") (class "Default")
      (node (ref "NET") (pin "A") (pinfunction "A_A") (pintype "passive"))
      (node (ref "R18") (pin "1") (pinfunction "1_1") (pintype "passive"))
    )
    (net (code "100") (name "Net-(Q1-G)") (class "Default")
      (node (ref "Q1") (pin "1") (pinfunction "G_1") (pintype "passive"))
      (node (ref "R31") (pin "1") (pinfunction "1_1") (pintype "passive"))
      (node (ref "R32") (pin "2") (pinfunction "2_2") (pintype "passive"))
    )
    (net (code "101") (name "Net-(Q3-G)") (class "Default")
      (node (ref "Q3") (pin "1") (pinfunction "G_1") (pintype "passive"))
      (node (ref "R35") (pin "1") (pinfunction "1_1") (pintype "passive"))
      (node (ref "R36") (pin "2") (pinfunction "2_2") (pintype "passive"))
    )
    (net (code "102") (name "Net-(Q4-D)") (class "Default")
      (node (ref "Q4") (pin "3") (pinfunction "D_3") (pintype "passive"))
      (node (ref "STA") (pin "C") (pinfunction "C_C") (pintype "passive"))
    )
    (net (code "103") (name "Net-(Q4-G)") (class "Default")
      (node (ref "Q4") (pin "1") (pinfunction "G_1") (pintype "passive"))
      (node (ref "R41") (pin "1") (pinfunction "1_1") (pintype "passive"))
      (node (ref "R42") (pin "2") (pinfunction "2_2") (pintype "passive"))
    )
    (net (code "104") (name "Net-(Q6-D)") (class "Default")
      (node (ref "NET") (pin "C") (pinfunction "C_C") (pintype "passive"))
      (node (ref "Q6") (pin "3") (pinfunction "D_3") (pintype "passive"))
    )
    (net (code "105") (name "Net-(Q6-G)") (class "Default")
      (node (ref "Q6") (pin "1") (pinfunction "G_1") (pintype "passive"))
      (node (ref "R14") (pin "2") (pinfunction "2_2") (pintype "passive"))
      (node (ref "R16") (pin "1") (pinfunction "1_1") (pintype "passive"))
    )
    (net (code "106") (name "Net-(Q10-B)") (class "Default")
      (node (ref "Q10") (pin "1") (pinfunction "B_1") (pintype "passive"))
      (node (ref "R63") (pin "1") (pinfunction "1_1") (pintype "passive"))
    )
    (net (code "107") (name "Net-(Q11-B)") (class "Default")
      (node (ref "Q11") (pin "1") (pinfunction "B_1") (pintype "passive"))
      (node (ref "R62") (pin "1") (pinfunction "1_1") (pintype "passive"))
    )
    (net (code "108") (name "Net-(R28-Pad2)") (class "Default")
      (node (ref "R28") (pin "2") (pinfunction "2_2") (pintype "passive"))
      (node (ref "USB-LTE") (pin "A6") (pinfunction "D+_A6") (pintype "bidirectional"))
      (node (ref "USB-LTE") (pin "B6") (pinfunction "D+_B6") (pintype "bidirectional"))
    )
    (net (code "109") (name "Net-(R29-Pad2)") (class "Default")
      (node (ref "R29") (pin "2") (pinfunction "2_2") (pintype "passive"))
      (node (ref "USB-LTE") (pin "A7") (pinfunction "D-_A7") (pintype "bidirectional"))
      (node (ref "USB-LTE") (pin "B7") (pinfunction "D-_B7") (pintype "bidirectional"))
    )
    (net (code "110") (name "Net-(R38-Pad1)") (class "Default")
      (node (ref "R38") (pin "1") (pinfunction "1_1") (pintype "passive"))
      (node (ref "STA") (pin "A") (pinfunction "A_A") (pintype "passive"))
    )
    (net (code "111") (name "Net-(R52-Pad1)") (class "Default")
      (node (ref "R52") (pin "1") (pinfunction "1_1") (pintype "passive"))
      (node (ref "U5") (pin "95") (pinfunction "NC_95") (pintype "bidirectional"))
    )
    (net (code "112") (name "Net-(R53-Pad1)") (class "Default")
      (node (ref "R53") (pin "1") (pinfunction "1_1") (pintype "passive"))
      (node (ref "U5") (pin "96") (pinfunction "NC_96") (pintype "bidirectional"))
    )
    (net (code "113") (name "Net-(SD-DATA1)") (class "Default")
      (node (ref "R72") (pin "1") (pinfunction "1_1") (pintype "passive"))
      (node (ref "SD") (pin "8") (pinfunction "DATA1_8") (pintype "bidirectional"))
    )
    (net (code "114") (name "Net-(SD-DATA2)") (class "Default")
      (node (ref "R70") (pin "1") (pinfunction "1_1") (pintype "passive"))
      (node (ref "SD") (pin "1") (pinfunction "DATA2_1") (pintype "bidirectional"))
    )
    (net (code "115") (name "Net-(U1-V)") (class "Default")
      (node (ref "R8") (pin "2") (pinfunction "2_2") (pintype "passive"))
      (node (ref "U1") (pin "1") (pinfunction "V_1") (pintype "bidirectional"))
    )
    (net (code "116") (name "Net-(U1-VDD)") (class "Default")
      (node (ref "C25") (pin "2") (pinfunction "2_2") (pintype "passive"))
      (node (ref "R11") (pin "2") (pinfunction "2_2") (pintype "passive"))
      (node (ref "U1") (pin "5") (pinfunction "VDD_5") (pintype "bidirectional"))
    )
    (net (code "117") (name "Net-(U3-CHRG)") (class "Default")
      (node (ref "R13") (pin "2") (pinfunction "2_2") (pintype "passive"))
      (node (ref "U3") (pin "7") (pinfunction "CHRG_7") (pintype "bidirectional"))
    )
    (net (code "118") (name "Net-(U3-DONE)") (class "Default")
      (node (ref "R17") (pin "2") (pinfunction "2_2") (pintype "passive"))
      (node (ref "U3") (pin "6") (pinfunction "DONE_6") (pintype "bidirectional"))
    )
    (net (code "119") (name "Net-(U3-ISET)") (class "Default")
      (node (ref "R12") (pin "1") (pinfunction "1_1") (pintype "passive"))
      (node (ref "U3") (pin "2") (pinfunction "ISET_2") (pintype "bidirectional"))
    )
    (net (code "120") (name "Net-(U5-USIM1_CLK)") (class "Default")
      (node (ref "R23") (pin "1") (pinfunction "1_1") (pintype "passive"))
      (node (ref "U5") (pin "32") (pinfunction "USIM1_CLK_32") (pintype "bidirectional"))
    )
    (net (code "121") (name "Net-(U5-USIM1_DATA)") (class "Default")
      (node (ref "R22") (pin "1") (pinfunction "1_1") (pintype "passive"))
      (node (ref "U5") (pin "31") (pinfunction "USIM1_DATA_31") (pintype "bidirectional"))
    )
    (net (code "122") (name "Net-(U5-USIM1_RST)") (class "Default")
      (node (ref "R24") (pin "1") (pinfunction "1_1") (pintype "passive"))
      (node (ref "U5") (pin "33") (pinfunction "USIM1_RST_33") (pintype "bidirectional"))
    )
    (net (code "123") (name "Net-(U7-RXD)") (class "Default")
      (node (ref "R69") (pin "2") (pinfunction "2_2") (pintype "passive"))
      (node (ref "U7") (pin "9") (pinfunction "RXD_9") (pintype "bidirectional"))
    )
    (net (code "124") (name "Net-(U7-TXD)") (class "Default")
      (node (ref "R68") (pin "2") (pinfunction "2_2") (pintype "passive"))
      (node (ref "U7") (pin "8") (pinfunction "TXD_8") (pintype "bidirectional"))
    )
    (net (code "125") (name "Net-(USB-LTE-CC1)") (class "Default")
      (node (ref "R27") (pin "2") (pinfunction "2_2") (pintype "passive"))
      (node (ref "USB-LTE") (pin "A5") (pinfunction "CC1_A5") (pintype "bidirectional"))
    )
    (net (code "126") (name "Net-(USB-LTE-CC2)") (class "Default")
      (node (ref "R26") (pin "2") (pinfunction "2_2") (pintype "passive"))
      (node (ref "USB-LTE") (pin "B5") (pinfunction "CC2_B5") (pintype "bidirectional"))
    )
    (net (code "127") (name "Net-(USB-NATIVE-CC1)") (class "Default")
      (node (ref "R61") (pin "2") (pinfunction "2_2") (pintype "passive"))
      (node (ref "USB-NATIVE") (pin "A5") (pinfunction "CC1_A5") (pintype "bidirectional"))
    )
    (net (code "128") (name "Net-(USB-NATIVE-CC2)") (class "Default")
      (node (ref "R60") (pin "2") (pinfunction "2_2") (pintype "passive"))
      (node (ref "USB-NATIVE") (pin "B5") (pinfunction "CC2_B5") (pintype "bidirectional"))
    )
    (net (code "129") (name "Net-(USB-TTL-CC1)") (class "Default")
      (node (ref "R67") (pin "2") (pinfunction "2_2") (pintype "passive"))
      (node (ref "USB-TTL") (pin "A5") (pinfunction "CC1_A5") (pintype "bidirectional"))
    )
    (net (code "130") (name "Net-(USB-TTL-CC2)") (class "Default")
      (node (ref "R64") (pin "2") (pinfunction "2_2") (pintype "passive"))
      (node (ref "USB-TTL") (pin "B5") (pinfunction "CC2_B5") (pintype "bidirectional"))
    )
    (net (code "131") (name "VBAT+") (class "Default")
      (node (ref "BAT") (pin "2") (pinfunction "2_2") (pintype "bidirectional"))
      (node (ref "C7") (pin "1") (pinfunction "1_1") (pintype "passive"))
      (node (ref "J3") (pin "1") (pinfunction "1_1") (pintype "passive"))
      (node (ref "J5") (pin "13") (pinfunction "13_13") (pintype "bidirectional"))
      (node (ref "R1") (pin "2") (pinfunction "2_2") (pintype "passive"))
      (node (ref "R11") (pin "1") (pinfunction "1_1") (pintype "passive"))
      (node (ref "SW1") (pin "COM1") (pinfunction "COM1_COM1") (pintype "bidirectional"))
      (node (ref "U3") (pin "5") (pinfunction "BAT_5") (pintype "bidirectional"))
    )
    (net (code "132") (name "VBUS") (class "Default")
      (node (ref "C49") (pin "2") (pinfunction "2_2") (pintype "passive"))
      (node (ref "C50") (pin "2") (pinfunction "2_2") (pintype "passive"))
      (node (ref "C54") (pin "2") (pinfunction "2_2") (pintype "passive"))
      (node (ref "D3") (pin "A") (pinfunction "A_A") (pintype "passive"))
      (node (ref "J1") (pin "1") (pinfunction "1_1") (pintype "bidirectional"))
      (node (ref "USB-TTL") (pin "VBUS1") (pinfunction "VBUS_VBUS1") (pintype "bidirectional"))
      (node (ref "USB-TTL") (pin "VBUS2") (pinfunction "VBUS_VBUS2") (pintype "bidirectional"))
    )
    (net (code "133") (name "VDD") (class "Default")
      (node (ref "3V") (pin "T") (pinfunction "T_T") (pintype "bidirectional"))
      (node (ref "C30") (pin "2") (pinfunction "2_2") (pintype "passive"))
      (node (ref "C31") (pin "2") (pinfunction "2_2") (pintype "passive"))
      (node (ref "R51") (pin "1") (pinfunction "1_1") (pintype "passive"))
      (node (ref "U5") (pin "99") (pinfunction "VDD_AUX_99") (pintype "bidirectional"))
    )
    (net (code "134") (name "V_BATT") (class "Default")
      (node (ref "C18") (pin "2") (pinfunction "2_2") (pintype "passive"))
      (node (ref "C19") (pin "2") (pinfunction "2_2") (pintype "passive"))
      (node (ref "C22") (pin "2") (pinfunction "2_2") (pintype "passive"))
      (node (ref "C23") (pin "2") (pinfunction "2_2") (pintype "passive"))
      (node (ref "C24") (pin "2") (pinfunction "2_2") (pintype "passive"))
      (node (ref "C26") (pin "A") (pinfunction "+_A") (pintype "passive"))
      (node (ref "C46") (pin "2") (pinfunction "2_2") (pintype "passive"))
      (node (ref "C47") (pin "2") (pinfunction "2_2") (pintype "passive"))
      (node (ref "C48") (pin "A") (pinfunction "+_A") (pintype "passive"))
      (node (ref "D7") (pin "-") (pinfunction "-_-") (pintype "passive"))
      (node (ref "D8") (pin "C") (pinfunction "C_C") (pintype "passive"))
      (node (ref "R18") (pin "2") (pinfunction "2_2") (pintype "passive"))
      (node (ref "R38") (pin "2") (pinfunction "2_2") (pintype "passive"))
      (node (ref "R6") (pin "1") (pinfunction "1_1") (pintype "passive"))
      (node (ref "U5") (pin "55") (pinfunction "VBAT_55") (pintype "bidirectional"))
      (node (ref "U5") (pin "56") (pinfunction "VBAT_56") (pintype "bidirectional"))
      (node (ref "U5") (pin "57") (pinfunction "VBAT_57") (pintype "bidirectional"))
    )
    (net (code "135") (name "unconnected-(D10-C1-Pad1)") (class "Default")
      (node (ref "D10") (pin "1") (pinfunction "C1_1") (pintype "passive"))
    )
    (net (code "136") (name "unconnected-(EAR-Pad5)") (class "Default")
      (node (ref "EAR") (pin "5") (pinfunction "5_5") (pintype "bidirectional"))
    )
    (net (code "137") (name "unconnected-(EAR-Pad6)") (class "Default")
      (node (ref "EAR") (pin "6") (pinfunction "6_6") (pintype "bidirectional"))
    )
    (net (code "138") (name "unconnected-(EAR-Pad7)") (class "Default")
      (node (ref "EAR") (pin "7") (pinfunction "7_7") (pintype "bidirectional"))
    )
    (net (code "139") (name "unconnected-(EAR-Pad8)") (class "Default")
      (node (ref "EAR") (pin "8") (pinfunction "8_8") (pintype "bidirectional"))
    )
    (net (code "140") (name "unconnected-(SD-CDN-Pad9)") (class "Default")
      (node (ref "SD") (pin "9") (pinfunction "CDN_9") (pintype "bidirectional"))
    )
    (net (code "141") (name "unconnected-(SIM-VPP-Pad6)") (class "Default")
      (node (ref "SIM") (pin "6") (pinfunction "VPP_6") (pintype "bidirectional"))
    )
    (net (code "142") (name "unconnected-(SW1-PadCH1B)") (class "Default")
      (node (ref "SW1") (pin "CH1B") (pinfunction "CH1B_CH1B") (pintype "bidirectional"))
    )
    (net (code "143") (name "unconnected-(SW1-PadCH2B)") (class "Default")
      (node (ref "SW1") (pin "CH2B") (pinfunction "CH2B_CH2B") (pintype "bidirectional"))
    )
    (net (code "144") (name "unconnected-(U1-D-Pad4)") (class "Default")
      (node (ref "U1") (pin "4") (pinfunction "D_4") (pintype "bidirectional"))
    )
    (net (code "145") (name "unconnected-(U4-BYP-Pad4)") (class "Default")
      (node (ref "U4") (pin "4") (pinfunction "BYP_4") (pintype "bidirectional"))
    )
    (net (code "146") (name "unconnected-(U5-ADC-Pad25)") (class "Default")
      (node (ref "U5") (pin "25") (pinfunction "ADC_25") (pintype "bidirectional"))
    )
    (net (code "147") (name "unconnected-(U5-CAM_I2C_SCL-Pad118)") (class "Default")
      (node (ref "U5") (pin "118") (pinfunction "CAM_I2C_SCL_118") (pintype "bidirectional"))
    )
    (net (code "148") (name "unconnected-(U5-CAM_I2C_SDA-Pad117)") (class "Default")
      (node (ref "U5") (pin "117") (pinfunction "CAM_I2C_SDA_117") (pintype "bidirectional"))
    )
    (net (code "149") (name "unconnected-(U5-CAM_MCLK-Pad121)") (class "Default")
      (node (ref "U5") (pin "121") (pinfunction "CAM_MCLK_121") (pintype "bidirectional"))
    )
    (net (code "150") (name "unconnected-(U5-CAM_PWDN-Pad119)") (class "Default")
      (node (ref "U5") (pin "119") (pinfunction "CAM_PWDN_119") (pintype "bidirectional"))
    )
    (net (code "151") (name "unconnected-(U5-CAM_RST-Pad120)") (class "Default")
      (node (ref "U5") (pin "120") (pinfunction "CAM_RST_120") (pintype "bidirectional"))
    )
    (net (code "152") (name "unconnected-(U5-CAM_SPI_CLK-Pad124)") (class "Default")
      (node (ref "U5") (pin "124") (pinfunction "CAM_SPI_CLK_124") (pintype "bidirectional"))
    )
    (net (code "153") (name "unconnected-(U5-CAM_SPI_D0-Pad122)") (class "Default")
      (node (ref "U5") (pin "122") (pinfunction "CAM_SPI_D0_122") (pintype "bidirectional"))
    )
    (net (code "154") (name "unconnected-(U5-CAM_SPI_D1-Pad123)") (class "Default")
      (node (ref "U5") (pin "123") (pinfunction "CAM_SPI_D1_123") (pintype "bidirectional"))
    )
    (net (code "155") (name "unconnected-(U5-CTS-Pad7)") (class "Default")
      (node (ref "U5") (pin "7") (pinfunction "CTS_7") (pintype "bidirectional"))
    )
    (net (code "156") (name "unconnected-(U5-DCD-Pad5)") (class "Default")
      (node (ref "U5") (pin "5") (pinfunction "DCD_5") (pintype "bidirectional"))
    )
    (net (code "157") (name "unconnected-(U5-GPIO1-Pad19)") (class "Default")
      (node (ref "U5") (pin "19") (pinfunction "GPIO1_19") (pintype "bidirectional"))
    )
    (net (code "158") (name "unconnected-(U5-GPIO2-Pad26)") (class "Default")
      (node (ref "U5") (pin "26") (pinfunction "GPIO2_26") (pintype "bidirectional"))
    )
    (net (code "159") (name "unconnected-(U5-GPIO3-Pad48)") (class "Default")
      (node (ref "U5") (pin "48") (pinfunction "GPIO3_48") (pintype "bidirectional"))
    )
    (net (code "160") (name "unconnected-(U5-GPIO4-Pad53)") (class "Default")
      (node (ref "U5") (pin "53") (pinfunction "GPIO4_53") (pintype "bidirectional"))
    )
    (net (code "161") (name "unconnected-(U5-I2C_SCL-Pad38)") (class "Default")
      (node (ref "U5") (pin "38") (pinfunction "I2C_SCL_38") (pintype "bidirectional"))
    )
    (net (code "162") (name "unconnected-(U5-I2C_SDA-Pad37)") (class "Default")
      (node (ref "U5") (pin "37") (pinfunction "I2C_SDA_37") (pintype "bidirectional"))
    )
    (net (code "163") (name "unconnected-(U5-LCD_BL_PWM-Pad101)") (class "Default")
      (node (ref "U5") (pin "101") (pinfunction "LCD_BL_PWM_101") (pintype "bidirectional"))
    )
    (net (code "164") (name "unconnected-(U5-LCD_DCX-Pad107)") (class "Default")
      (node (ref "U5") (pin "107") (pinfunction "LCD_DCX_107") (pintype "bidirectional"))
    )
    (net (code "165") (name "unconnected-(U5-LCD_RST-Pad106)") (class "Default")
      (node (ref "U5") (pin "106") (pinfunction "LCD_RST_106") (pintype "bidirectional"))
    )
    (net (code "166") (name "unconnected-(U5-LCD_SPI_CLK-Pad102)") (class "Default")
      (node (ref "U5") (pin "102") (pinfunction "LCD_SPI_CLK_102") (pintype "bidirectional"))
    )
    (net (code "167") (name "unconnected-(U5-LCD_SPI_CS-Pad105)") (class "Default")
      (node (ref "U5") (pin "105") (pinfunction "LCD_SPI_CS_105") (pintype "bidirectional"))
    )
    (net (code "168") (name "unconnected-(U5-LCD_SPI_RXD-Pad104)") (class "Default")
      (node (ref "U5") (pin "104") (pinfunction "LCD_SPI_RXD_104") (pintype "bidirectional"))
    )
    (net (code "169") (name "unconnected-(U5-LCD_SPI_TXD-Pad103)") (class "Default")
      (node (ref "U5") (pin "103") (pinfunction "LCD_SPI_TXD_103") (pintype "bidirectional"))
    )
    (net (code "170") (name "unconnected-(U5-MK_IN_2-Pad47)") (class "Default")
      (node (ref "U5") (pin "47") (pinfunction "MK_IN_2_47") (pintype "bidirectional"))
    )
    (net (code "171") (name "unconnected-(U5-MK_IN_5-Pad68)") (class "Default")
      (node (ref "U5") (pin "68") (pinfunction "MK_IN_5_68") (pintype "bidirectional"))
    )
    (net (code "172") (name "unconnected-(U5-MK_IN_6-Pad36)") (class "Default")
      (node (ref "U5") (pin "36") (pinfunction "MK_IN_6_36") (pintype "bidirectional"))
    )
    (net (code "173") (name "unconnected-(U5-MK_OUT_2-Pad44)") (class "Default")
      (node (ref "U5") (pin "44") (pinfunction "MK_OUT_2_44") (pintype "bidirectional"))
    )
    (net (code "174") (name "unconnected-(U5-MK_OUT_3-Pad21)") (class "Default")
      (node (ref "U5") (pin "21") (pinfunction "MK_OUT_3_21") (pintype "bidirectional"))
    )
    (net (code "175") (name "unconnected-(U5-MK_OUT_5-Pad67)") (class "Default")
      (node (ref "U5") (pin "67") (pinfunction "MK_OUT_5_67") (pintype "bidirectional"))
    )
    (net (code "176") (name "unconnected-(U5-MK_OUT_6-Pad35)") (class "Default")
      (node (ref "U5") (pin "35") (pinfunction "MK_OUT_6_35") (pintype "bidirectional"))
    )
    (net (code "177") (name "unconnected-(U5-NC-Pad93)") (class "Default")
      (node (ref "U5") (pin "93") (pinfunction "NC_93") (pintype "bidirectional"))
    )
    (net (code "178") (name "unconnected-(U5-NC-Pad100)") (class "Default")
      (node (ref "U5") (pin "100") (pinfunction "NC_100") (pintype "bidirectional"))
    )
    (net (code "179") (name "unconnected-(U5-NC-Pad113)") (class "Default")
      (node (ref "U5") (pin "113") (pinfunction "NC_113") (pintype "bidirectional"))
    )
    (net (code "180") (name "unconnected-(U5-NC-Pad114)") (class "Default")
      (node (ref "U5") (pin "114") (pinfunction "NC_114") (pintype "bidirectional"))
    )
    (net (code "181") (name "unconnected-(U5-NC-Pad115)") (class "Default")
      (node (ref "U5") (pin "115") (pinfunction "NC_115") (pintype "bidirectional"))
    )
    (net (code "182") (name "unconnected-(U5-RTS-Pad8)") (class "Default")
      (node (ref "U5") (pin "8") (pinfunction "RTS_8") (pintype "bidirectional"))
    )
    (net (code "183") (name "unconnected-(U5-SPI_CLK-Pad11)") (class "Default")
      (node (ref "U5") (pin "11") (pinfunction "SPI_CLK_11") (pintype "bidirectional"))
    )
    (net (code "184") (name "unconnected-(U5-SPI_CS-Pad12)") (class "Default")
      (node (ref "U5") (pin "12") (pinfunction "SPI_CS_12") (pintype "bidirectional"))
    )
    (net (code "185") (name "unconnected-(U5-SPI_MISO-Pad14)") (class "Default")
      (node (ref "U5") (pin "14") (pinfunction "SPI_MISO_14") (pintype "bidirectional"))
    )
    (net (code "186") (name "unconnected-(U5-SPI_MOSI-Pad13)") (class "Default")
      (node (ref "U5") (pin "13") (pinfunction "SPI_MOSI_13") (pintype "bidirectional"))
    )
    (net (code "187") (name "unconnected-(U5-USIM1_DET-Pad34)") (class "Default")
      (node (ref "U5") (pin "34") (pinfunction "USIM1_DET_34") (pintype "bidirectional"))
    )
    (net (code "188") (name "unconnected-(U5-USIM2_CLK-Pad109)") (class "Default")
      (node (ref "U5") (pin "109") (pinfunction "USIM2_CLK_109") (pintype "bidirectional"))
    )
    (net (code "189") (name "unconnected-(U5-USIM2_DATA-Pad108)") (class "Default")
      (node (ref "U5") (pin "108") (pinfunction "USIM2_DATA_108") (pintype "bidirectional"))
    )
    (net (code "190") (name "unconnected-(U5-USIM2_DET-Pad112)") (class "Default")
      (node (ref "U5") (pin "112") (pinfunction "USIM2_DET_112") (pintype "bidirectional"))
    )
    (net (code "191") (name "unconnected-(U5-USIM2_RST-Pad111)") (class "Default")
      (node (ref "U5") (pin "111") (pinfunction "USIM2_RST_111") (pintype "bidirectional"))
    )
    (net (code "192") (name "unconnected-(U5-USIM2_VDD-Pad110)") (class "Default")
      (node (ref "U5") (pin "110") (pinfunction "USIM2_VDD_110") (pintype "bidirectional"))
    )
    (net (code "193") (name "unconnected-(U6-IO35-Pad28)") (class "Default")
      (node (ref "U6") (pin "28") (pinfunction "IO35_28") (pintype "bidirectional"))
    )
    (net (code "194") (name "unconnected-(U6-IO36-Pad29)") (class "Default")
      (node (ref "U6") (pin "29") (pinfunction "IO36_29") (pintype "bidirectional"))
    )
    (net (code "195") (name "unconnected-(U6-IO37-Pad30)") (class "Default")
      (node (ref "U6") (pin "30") (pinfunction "IO37_30") (pintype "bidirectional"))
    )
    (net (code "196") (name "unconnected-(U7-CTS#-Pad5)") (class "Default")
      (node (ref "U7") (pin "5") (pinfunction "CTS#_5") (pintype "bidirectional"))
    )
  )
)
